# FPGA_APU.net
KiCad netlist of a schematic drawn in EAGLE
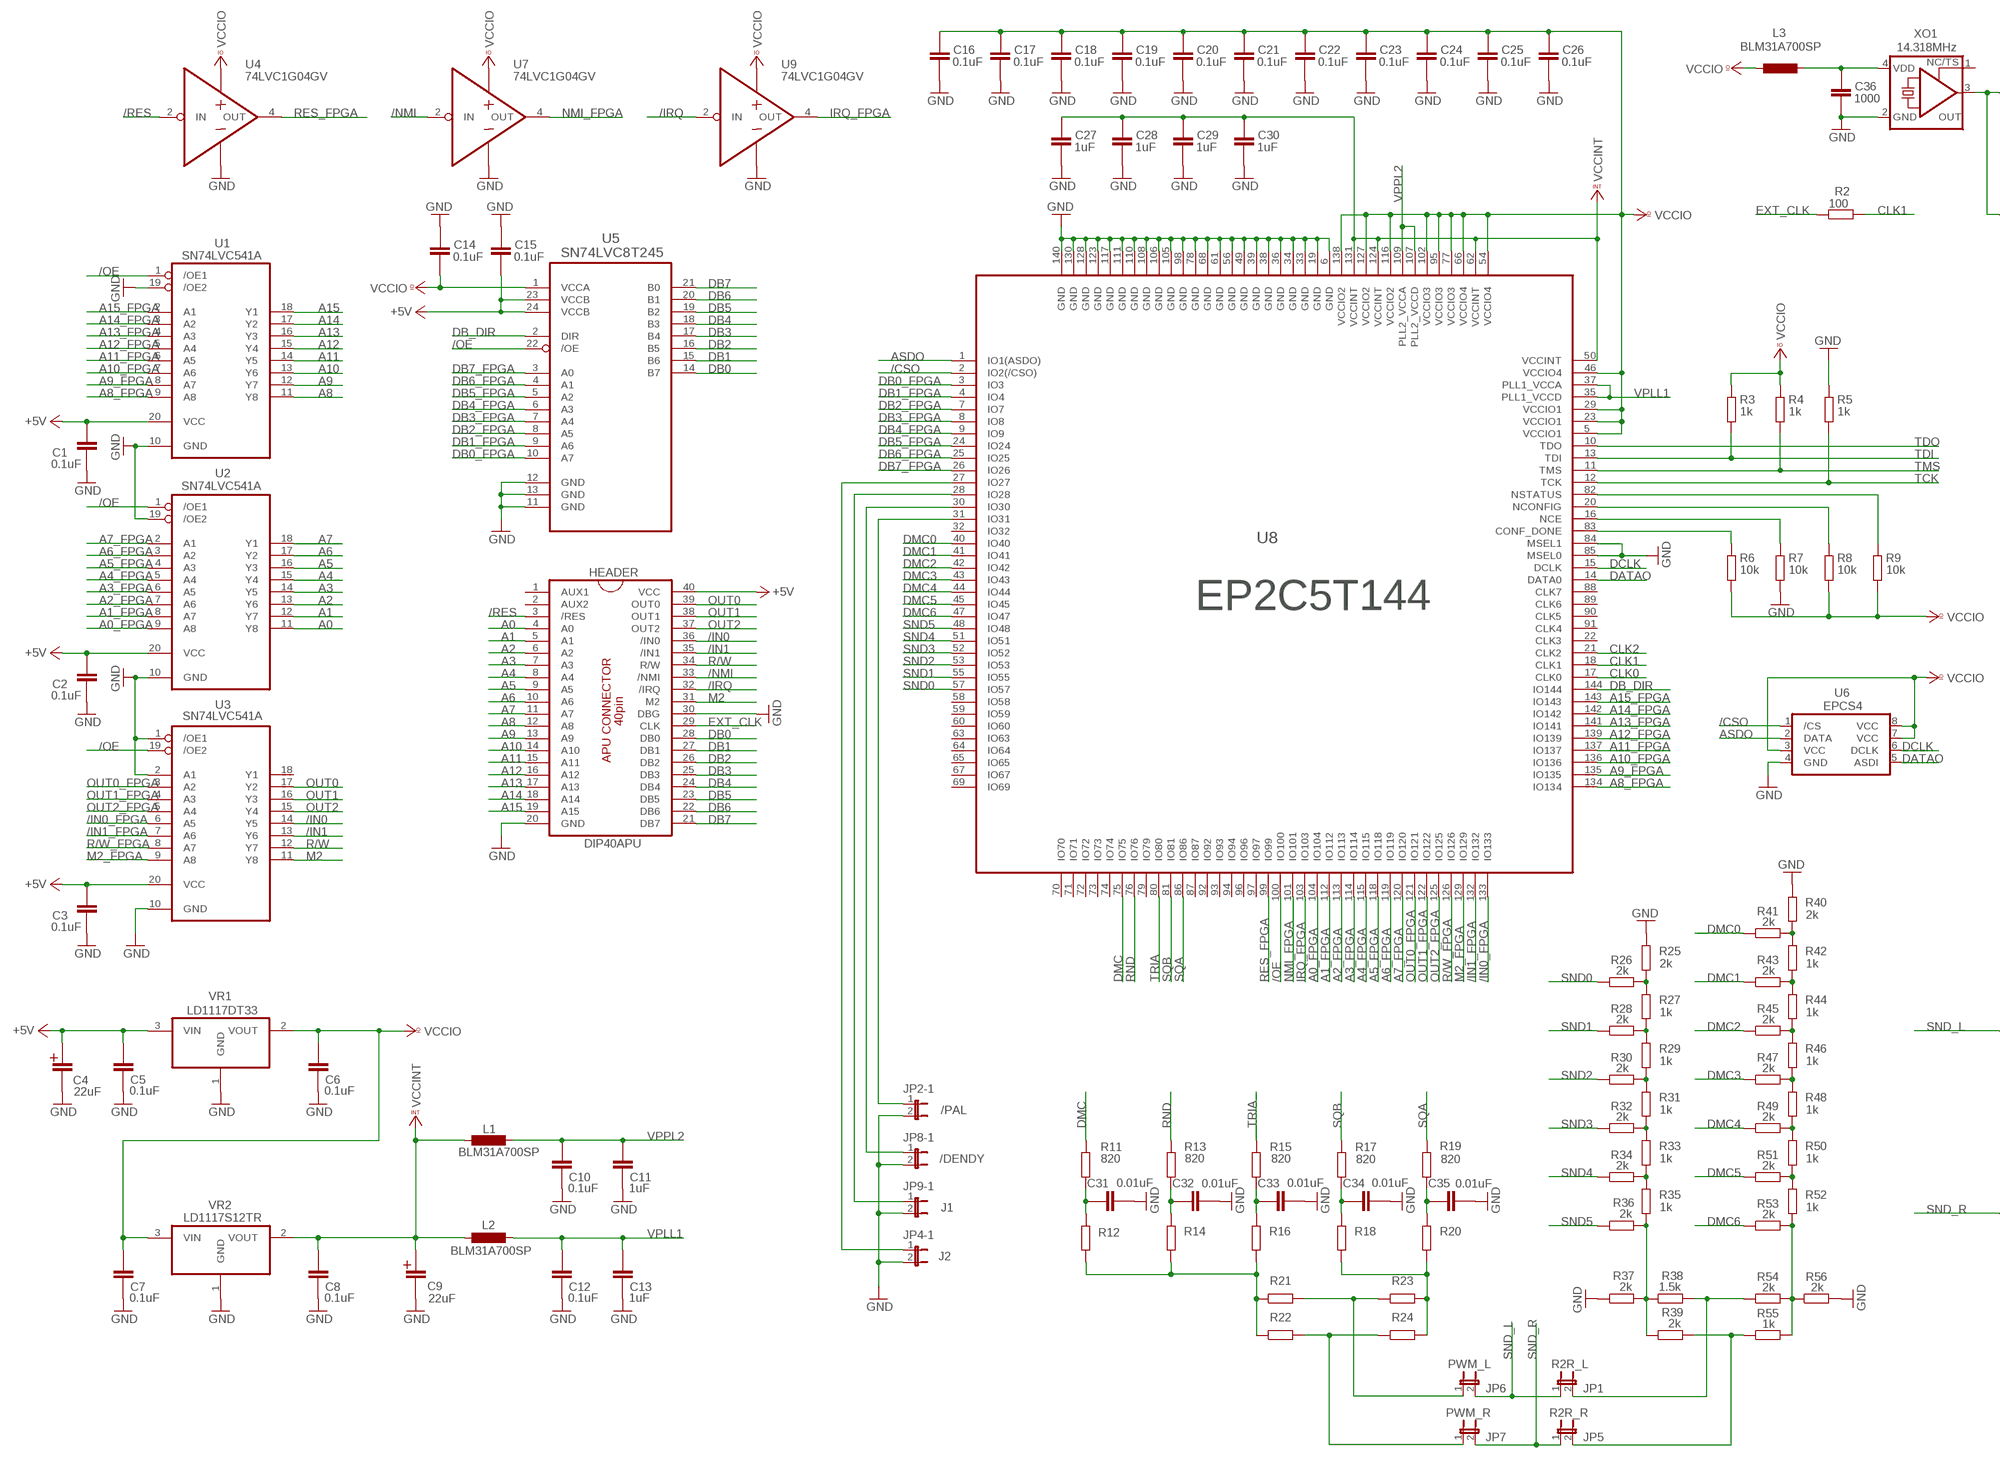
[diagram p0: schematic, sheet 1, part 1 of 2]
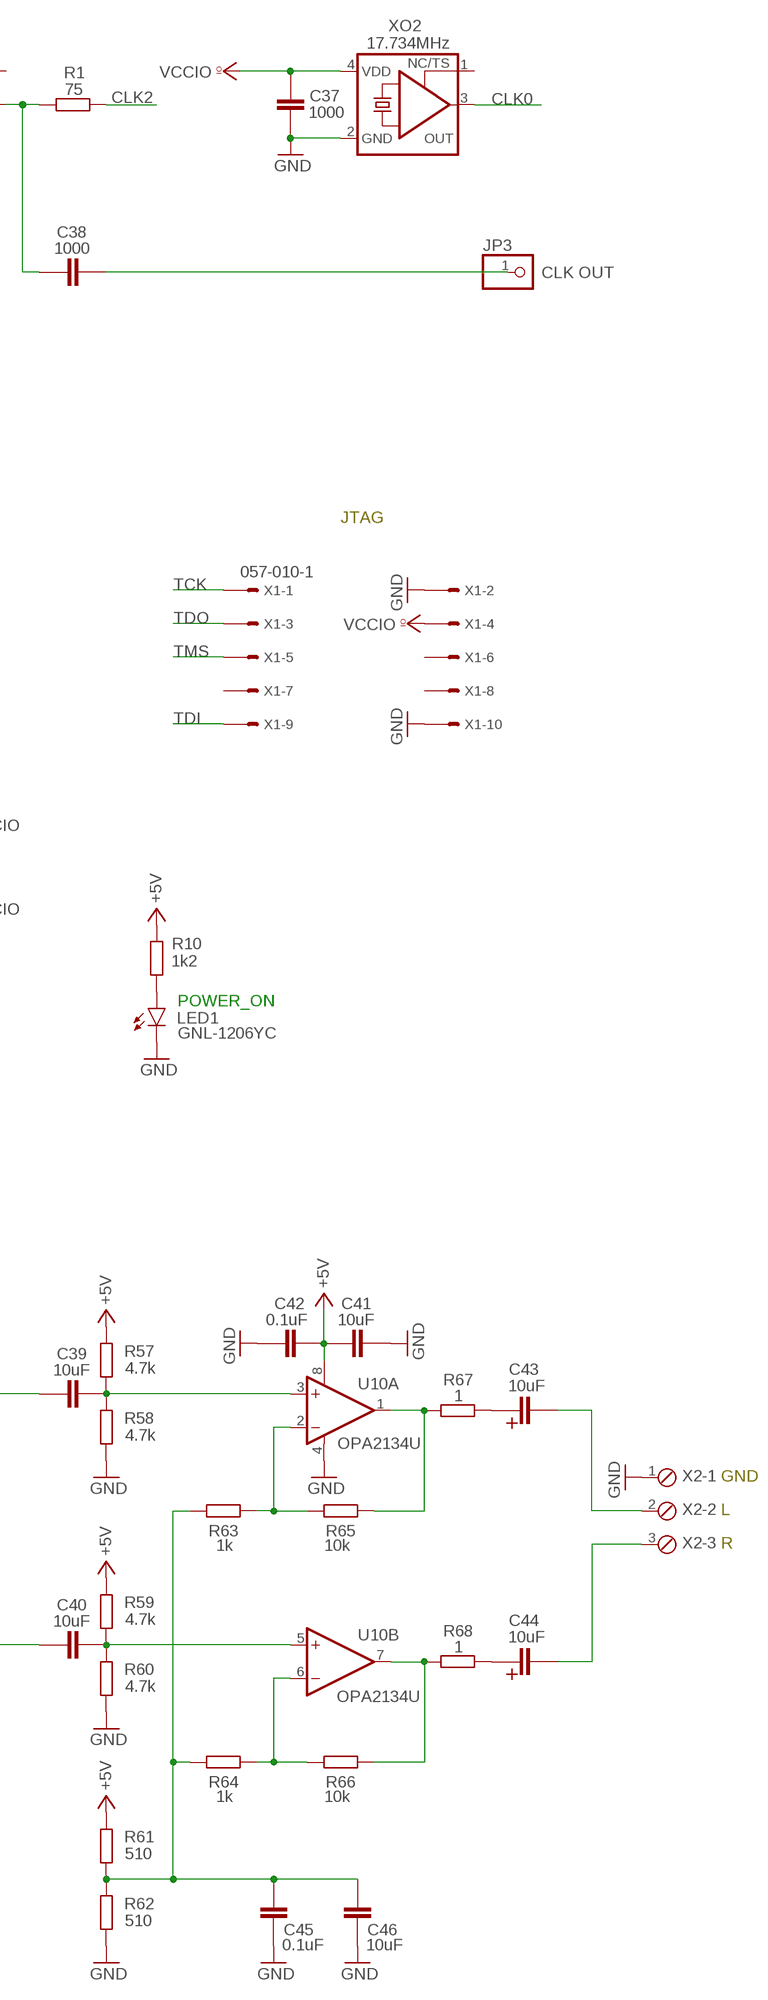
[diagram p1: schematic, sheet 1, part 2 of 2]

(export (version "E")
  (design (tool "Eeschema 10.0.6"))
  (components
    (comp (ref "C1")
      (value "0.1uF")
      (footprint "eagle-import:C0805")
      (libsource (lib "eagle-import") (part "C-EUC0805"))
    )
    (comp (ref "C2")
      (value "0.1uF")
      (footprint "eagle-import:C0805")
      (libsource (lib "eagle-import") (part "C-EUC0805"))
    )
    (comp (ref "C3")
      (value "0.1uF")
      (footprint "eagle-import:C0805")
      (libsource (lib "eagle-import") (part "C-EUC0805"))
    )
    (comp (ref "C4")
      (value "22uF")
      (footprint "eagle-import:153CLV-0505")
      (libsource (lib "eagle-import") (part "CPOL-EU153CLV-0505"))
    )
    (comp (ref "C5")
      (value "0.1uF")
      (footprint "eagle-import:C0805")
      (libsource (lib "eagle-import") (part "C-EUC0805"))
    )
    (comp (ref "C6")
      (value "0.1uF")
      (footprint "eagle-import:C0805")
      (libsource (lib "eagle-import") (part "C-EUC0805"))
    )
    (comp (ref "C7")
      (value "0.1uF")
      (footprint "eagle-import:C0805")
      (libsource (lib "eagle-import") (part "C-EUC0805"))
    )
    (comp (ref "C8")
      (value "0.1uF")
      (footprint "eagle-import:C0805")
      (libsource (lib "eagle-import") (part "C-EUC0805"))
    )
    (comp (ref "C9")
      (value "22uF")
      (footprint "eagle-import:153CLV-0505")
      (libsource (lib "eagle-import") (part "CPOL-EU153CLV-0505"))
    )
    (comp (ref "C10")
      (value "0.1uF")
      (footprint "eagle-import:C0805")
      (libsource (lib "eagle-import") (part "C-EUC0805"))
    )
    (comp (ref "C11")
      (value "1uF")
      (footprint "eagle-import:C0805")
      (libsource (lib "eagle-import") (part "C-EUC0805"))
    )
    (comp (ref "C12")
      (value "0.1uF")
      (footprint "eagle-import:C0805")
      (libsource (lib "eagle-import") (part "C-EUC0805"))
    )
    (comp (ref "C13")
      (value "1uF")
      (footprint "eagle-import:C0805")
      (libsource (lib "eagle-import") (part "C-EUC0805"))
    )
    (comp (ref "C14")
      (value "0.1uF")
      (footprint "eagle-import:C0805")
      (libsource (lib "eagle-import") (part "C-EUC0805"))
    )
    (comp (ref "C15")
      (value "0.1uF")
      (footprint "eagle-import:C0805")
      (libsource (lib "eagle-import") (part "C-EUC0805"))
    )
    (comp (ref "C16")
      (value "0.1uF")
      (footprint "eagle-import:C0805")
      (libsource (lib "eagle-import") (part "C-EUC0805"))
    )
    (comp (ref "C17")
      (value "0.1uF")
      (footprint "eagle-import:C0805")
      (libsource (lib "eagle-import") (part "C-EUC0805"))
    )
    (comp (ref "C18")
      (value "0.1uF")
      (footprint "eagle-import:C0805")
      (libsource (lib "eagle-import") (part "C-EUC0805"))
    )
    (comp (ref "C19")
      (value "0.1uF")
      (footprint "eagle-import:C0805")
      (libsource (lib "eagle-import") (part "C-EUC0805"))
    )
    (comp (ref "C20")
      (value "0.1uF")
      (footprint "eagle-import:C0805")
      (libsource (lib "eagle-import") (part "C-EUC0805"))
    )
    (comp (ref "C21")
      (value "0.1uF")
      (footprint "eagle-import:C0805")
      (libsource (lib "eagle-import") (part "C-EUC0805"))
    )
    (comp (ref "C22")
      (value "0.1uF")
      (footprint "eagle-import:C0805")
      (libsource (lib "eagle-import") (part "C-EUC0805"))
    )
    (comp (ref "C23")
      (value "0.1uF")
      (footprint "eagle-import:C0805")
      (libsource (lib "eagle-import") (part "C-EUC0805"))
    )
    (comp (ref "C24")
      (value "0.1uF")
      (footprint "eagle-import:C0805")
      (libsource (lib "eagle-import") (part "C-EUC0805"))
    )
    (comp (ref "C25")
      (value "0.1uF")
      (footprint "eagle-import:C0805")
      (libsource (lib "eagle-import") (part "C-EUC0805"))
    )
    (comp (ref "C26")
      (value "0.1uF")
      (footprint "eagle-import:C0805")
      (libsource (lib "eagle-import") (part "C-EUC0805"))
    )
    (comp (ref "C27")
      (value "1uF")
      (footprint "eagle-import:C0805")
      (libsource (lib "eagle-import") (part "C-EUC0805"))
    )
    (comp (ref "C28")
      (value "1uF")
      (footprint "eagle-import:C0805")
      (libsource (lib "eagle-import") (part "C-EUC0805"))
    )
    (comp (ref "C29")
      (value "1uF")
      (footprint "eagle-import:C0805")
      (libsource (lib "eagle-import") (part "C-EUC0805"))
    )
    (comp (ref "C30")
      (value "1uF")
      (footprint "eagle-import:C0805")
      (libsource (lib "eagle-import") (part "C-EUC0805"))
    )
    (comp (ref "C31")
      (value "0.01uF")
      (footprint "eagle-import:C0805")
      (libsource (lib "eagle-import") (part "C-EUC0805"))
    )
    (comp (ref "C32")
      (value "0.01uF")
      (footprint "eagle-import:C0805")
      (libsource (lib "eagle-import") (part "C-EUC0805"))
    )
    (comp (ref "C33")
      (value "0.01uF")
      (footprint "eagle-import:C0805")
      (libsource (lib "eagle-import") (part "C-EUC0805"))
    )
    (comp (ref "C34")
      (value "0.01uF")
      (footprint "eagle-import:C0805")
      (libsource (lib "eagle-import") (part "C-EUC0805"))
    )
    (comp (ref "C35")
      (value "0.01uF")
      (footprint "eagle-import:C0805")
      (libsource (lib "eagle-import") (part "C-EUC0805"))
    )
    (comp (ref "C36")
      (value "1000")
      (footprint "eagle-import:C0805")
      (libsource (lib "eagle-import") (part "C-EUC0805"))
    )
    (comp (ref "C37")
      (value "1000")
      (footprint "eagle-import:C0805")
      (libsource (lib "eagle-import") (part "C-EUC0805"))
    )
    (comp (ref "C38")
      (value "1000")
      (footprint "eagle-import:C0805")
      (libsource (lib "eagle-import") (part "C-EUC0805"))
    )
    (comp (ref "C39")
      (value "10uF")
      (footprint "eagle-import:C0805")
      (libsource (lib "eagle-import") (part "C-EUC0805"))
    )
    (comp (ref "C40")
      (value "10uF")
      (footprint "eagle-import:C0805")
      (libsource (lib "eagle-import") (part "C-EUC0805"))
    )
    (comp (ref "C41")
      (value "10uF")
      (footprint "eagle-import:C0805")
      (libsource (lib "eagle-import") (part "C-EUC0805"))
    )
    (comp (ref "C42")
      (value "0.1uF")
      (footprint "eagle-import:C0805")
      (libsource (lib "eagle-import") (part "C-EUC0805"))
    )
    (comp (ref "C43")
      (value "10uF")
      (footprint "eagle-import:153CLV-0505")
      (libsource (lib "eagle-import") (part "CPOL-EU153CLV-0505"))
    )
    (comp (ref "C44")
      (value "10uF")
      (footprint "eagle-import:153CLV-0505")
      (libsource (lib "eagle-import") (part "CPOL-EU153CLV-0505"))
    )
    (comp (ref "C45")
      (value "0.1uF")
      (footprint "eagle-import:C0805")
      (libsource (lib "eagle-import") (part "C-EUC0805"))
    )
    (comp (ref "C46")
      (value "10uF")
      (footprint "eagle-import:C0805")
      (libsource (lib "eagle-import") (part "C-EUC0805"))
    )
    (comp (ref "HEADER")
      (value "DIP40APU")
      (footprint "eagle-import:DIP-40")
      (libsource (lib "eagle-import") (part "DIP40APU"))
    )
    (comp (ref "JP1")
      (value "R2R_L")
      (footprint "eagle-import:JP1")
      (libsource (lib "eagle-import") (part "JP1E"))
    )
    (comp (ref "JP2")
      (value "/PAL")
      (footprint "eagle-import:JP4Q")
      (libsource (lib "eagle-import") (part "JP4QE"))
    )
    (comp (ref "JP3")
      (value "CLK OUT")
      (footprint "eagle-import:1X01")
      (libsource (lib "eagle-import") (part "PINHD-1X1"))
    )
    (comp (ref "JP4")
      (value "J2")
      (footprint "eagle-import:JP4Q")
      (libsource (lib "eagle-import") (part "JP4QE"))
    )
    (comp (ref "JP5")
      (value "R2R_R")
      (footprint "eagle-import:JP1")
      (libsource (lib "eagle-import") (part "JP1E"))
    )
    (comp (ref "JP6")
      (value "PWM_L")
      (footprint "eagle-import:JP1")
      (libsource (lib "eagle-import") (part "JP1E"))
    )
    (comp (ref "JP7")
      (value "PWM_R")
      (footprint "eagle-import:JP1")
      (libsource (lib "eagle-import") (part "JP1E"))
    )
    (comp (ref "JP8")
      (value "/DENDY")
      (footprint "eagle-import:JP4Q")
      (libsource (lib "eagle-import") (part "JP4QE"))
    )
    (comp (ref "JP9")
      (value "J1")
      (footprint "eagle-import:JP4Q")
      (libsource (lib "eagle-import") (part "JP4QE"))
    )
    (comp (ref "L1")
      (value "BLM31A700SP")
      (footprint "eagle-import:L2012C")
      (libsource (lib "eagle-import") (part "L-EUL2012C"))
    )
    (comp (ref "L2")
      (value "BLM31A700SP")
      (footprint "eagle-import:L2012C")
      (libsource (lib "eagle-import") (part "L-EUL2012C"))
    )
    (comp (ref "L3")
      (value "BLM31A700SP")
      (footprint "eagle-import:L2012C")
      (libsource (lib "eagle-import") (part "L-EUL2012C"))
    )
    (comp (ref "LED1")
      (value "GNL-1206YC")
      (footprint "eagle-import:SMARTLED-TTW")
      (libsource (lib "eagle-import") (part "LED"))
    )
    (comp (ref "R1")
      (value "75")
      (footprint "eagle-import:R0805")
      (libsource (lib "eagle-import") (part "R-EU_R0805"))
    )
    (comp (ref "R2")
      (value "100")
      (footprint "eagle-import:R0805")
      (libsource (lib "eagle-import") (part "R-EU_R0805"))
    )
    (comp (ref "R3")
      (value "1k")
      (footprint "eagle-import:R0805")
      (libsource (lib "eagle-import") (part "R-EU_R0805"))
    )
    (comp (ref "R4")
      (value "1k")
      (footprint "eagle-import:R0805")
      (libsource (lib "eagle-import") (part "R-EU_R0805"))
    )
    (comp (ref "R5")
      (value "1k")
      (footprint "eagle-import:R0805")
      (libsource (lib "eagle-import") (part "R-EU_R0805"))
    )
    (comp (ref "R6")
      (value "10k")
      (footprint "eagle-import:R0805")
      (libsource (lib "eagle-import") (part "R-EU_R0805"))
    )
    (comp (ref "R7")
      (value "10k")
      (footprint "eagle-import:R0805")
      (libsource (lib "eagle-import") (part "R-EU_R0805"))
    )
    (comp (ref "R8")
      (value "10k")
      (footprint "eagle-import:R0805")
      (libsource (lib "eagle-import") (part "R-EU_R0805"))
    )
    (comp (ref "R9")
      (value "10k")
      (footprint "eagle-import:R0805")
      (libsource (lib "eagle-import") (part "R-EU_R0805"))
    )
    (comp (ref "R10")
      (value "1k2")
      (footprint "eagle-import:R0805")
      (libsource (lib "eagle-import") (part "R-EU_R0805"))
    )
    (comp (ref "R11")
      (value "820")
      (footprint "eagle-import:R0805")
      (libsource (lib "eagle-import") (part "R-EU_R0805"))
    )
    (comp (ref "R12")
      (value "R-EU_R0805")
      (footprint "eagle-import:R0805")
      (libsource (lib "eagle-import") (part "R-EU_R0805"))
    )
    (comp (ref "R13")
      (value "820")
      (footprint "eagle-import:R0805")
      (libsource (lib "eagle-import") (part "R-EU_R0805"))
    )
    (comp (ref "R14")
      (value "R-EU_R0805")
      (footprint "eagle-import:R0805")
      (libsource (lib "eagle-import") (part "R-EU_R0805"))
    )
    (comp (ref "R15")
      (value "820")
      (footprint "eagle-import:R0805")
      (libsource (lib "eagle-import") (part "R-EU_R0805"))
    )
    (comp (ref "R16")
      (value "R-EU_R0805")
      (footprint "eagle-import:R0805")
      (libsource (lib "eagle-import") (part "R-EU_R0805"))
    )
    (comp (ref "R17")
      (value "820")
      (footprint "eagle-import:R0805")
      (libsource (lib "eagle-import") (part "R-EU_R0805"))
    )
    (comp (ref "R18")
      (value "R-EU_R0805")
      (footprint "eagle-import:R0805")
      (libsource (lib "eagle-import") (part "R-EU_R0805"))
    )
    (comp (ref "R19")
      (value "820")
      (footprint "eagle-import:R0805")
      (libsource (lib "eagle-import") (part "R-EU_R0805"))
    )
    (comp (ref "R20")
      (value "R-EU_R0805")
      (footprint "eagle-import:R0805")
      (libsource (lib "eagle-import") (part "R-EU_R0805"))
    )
    (comp (ref "R21")
      (value "R-EU_R0805")
      (footprint "eagle-import:R0805")
      (libsource (lib "eagle-import") (part "R-EU_R0805"))
    )
    (comp (ref "R22")
      (value "R-EU_R0805")
      (footprint "eagle-import:R0805")
      (libsource (lib "eagle-import") (part "R-EU_R0805"))
    )
    (comp (ref "R23")
      (value "R-EU_R0805")
      (footprint "eagle-import:R0805")
      (libsource (lib "eagle-import") (part "R-EU_R0805"))
    )
    (comp (ref "R24")
      (value "R-EU_R0805")
      (footprint "eagle-import:R0805")
      (libsource (lib "eagle-import") (part "R-EU_R0805"))
    )
    (comp (ref "R25")
      (value "2k")
      (footprint "eagle-import:R0805")
      (libsource (lib "eagle-import") (part "R-EU_R0805"))
    )
    (comp (ref "R26")
      (value "2k")
      (footprint "eagle-import:R0805")
      (libsource (lib "eagle-import") (part "R-EU_R0805"))
    )
    (comp (ref "R27")
      (value "1k")
      (footprint "eagle-import:R0805")
      (libsource (lib "eagle-import") (part "R-EU_R0805"))
    )
    (comp (ref "R28")
      (value "2k")
      (footprint "eagle-import:R0805")
      (libsource (lib "eagle-import") (part "R-EU_R0805"))
    )
    (comp (ref "R29")
      (value "1k")
      (footprint "eagle-import:R0805")
      (libsource (lib "eagle-import") (part "R-EU_R0805"))
    )
    (comp (ref "R30")
      (value "2k")
      (footprint "eagle-import:R0805")
      (libsource (lib "eagle-import") (part "R-EU_R0805"))
    )
    (comp (ref "R31")
      (value "1k")
      (footprint "eagle-import:R0805")
      (libsource (lib "eagle-import") (part "R-EU_R0805"))
    )
    (comp (ref "R32")
      (value "2k")
      (footprint "eagle-import:R0805")
      (libsource (lib "eagle-import") (part "R-EU_R0805"))
    )
    (comp (ref "R33")
      (value "1k")
      (footprint "eagle-import:R0805")
      (libsource (lib "eagle-import") (part "R-EU_R0805"))
    )
    (comp (ref "R34")
      (value "2k")
      (footprint "eagle-import:R0805")
      (libsource (lib "eagle-import") (part "R-EU_R0805"))
    )
    (comp (ref "R35")
      (value "1k")
      (footprint "eagle-import:R0805")
      (libsource (lib "eagle-import") (part "R-EU_R0805"))
    )
    (comp (ref "R36")
      (value "2k")
      (footprint "eagle-import:R0805")
      (libsource (lib "eagle-import") (part "R-EU_R0805"))
    )
    (comp (ref "R37")
      (value "2k")
      (footprint "eagle-import:R0805")
      (libsource (lib "eagle-import") (part "R-EU_R0805"))
    )
    (comp (ref "R38")
      (value "1.5k")
      (footprint "eagle-import:R0805")
      (libsource (lib "eagle-import") (part "R-EU_R0805"))
    )
    (comp (ref "R39")
      (value "2k")
      (footprint "eagle-import:R0805")
      (libsource (lib "eagle-import") (part "R-EU_R0805"))
    )
    (comp (ref "R40")
      (value "2k")
      (footprint "eagle-import:R0805")
      (libsource (lib "eagle-import") (part "R-EU_R0805"))
    )
    (comp (ref "R41")
      (value "2k")
      (footprint "eagle-import:R0805")
      (libsource (lib "eagle-import") (part "R-EU_R0805"))
    )
    (comp (ref "R42")
      (value "1k")
      (footprint "eagle-import:R0805")
      (libsource (lib "eagle-import") (part "R-EU_R0805"))
    )
    (comp (ref "R43")
      (value "2k")
      (footprint "eagle-import:R0805")
      (libsource (lib "eagle-import") (part "R-EU_R0805"))
    )
    (comp (ref "R44")
      (value "1k")
      (footprint "eagle-import:R0805")
      (libsource (lib "eagle-import") (part "R-EU_R0805"))
    )
    (comp (ref "R45")
      (value "2k")
      (footprint "eagle-import:R0805")
      (libsource (lib "eagle-import") (part "R-EU_R0805"))
    )
    (comp (ref "R46")
      (value "1k")
      (footprint "eagle-import:R0805")
      (libsource (lib "eagle-import") (part "R-EU_R0805"))
    )
    (comp (ref "R47")
      (value "2k")
      (footprint "eagle-import:R0805")
      (libsource (lib "eagle-import") (part "R-EU_R0805"))
    )
    (comp (ref "R48")
      (value "1k")
      (footprint "eagle-import:R0805")
      (libsource (lib "eagle-import") (part "R-EU_R0805"))
    )
    (comp (ref "R49")
      (value "2k")
      (footprint "eagle-import:R0805")
      (libsource (lib "eagle-import") (part "R-EU_R0805"))
    )
    (comp (ref "R50")
      (value "1k")
      (footprint "eagle-import:R0805")
      (libsource (lib "eagle-import") (part "R-EU_R0805"))
    )
    (comp (ref "R51")
      (value "2k")
      (footprint "eagle-import:R0805")
      (libsource (lib "eagle-import") (part "R-EU_R0805"))
    )
    (comp (ref "R52")
      (value "1k")
      (footprint "eagle-import:R0805")
      (libsource (lib "eagle-import") (part "R-EU_R0805"))
    )
    (comp (ref "R53")
      (value "2k")
      (footprint "eagle-import:R0805")
      (libsource (lib "eagle-import") (part "R-EU_R0805"))
    )
    (comp (ref "R54")
      (value "2k")
      (footprint "eagle-import:R0805")
      (libsource (lib "eagle-import") (part "R-EU_R0805"))
    )
    (comp (ref "R55")
      (value "1k")
      (footprint "eagle-import:R0805")
      (libsource (lib "eagle-import") (part "R-EU_R0805"))
    )
    (comp (ref "R56")
      (value "2k")
      (footprint "eagle-import:R0805")
      (libsource (lib "eagle-import") (part "R-EU_R0805"))
    )
    (comp (ref "R57")
      (value "4.7k")
      (footprint "eagle-import:R0805")
      (libsource (lib "eagle-import") (part "R-EU_R0805"))
    )
    (comp (ref "R58")
      (value "4.7k")
      (footprint "eagle-import:R0805")
      (libsource (lib "eagle-import") (part "R-EU_R0805"))
    )
    (comp (ref "R59")
      (value "4.7k")
      (footprint "eagle-import:R0805")
      (libsource (lib "eagle-import") (part "R-EU_R0805"))
    )
    (comp (ref "R60")
      (value "4.7k")
      (footprint "eagle-import:R0805")
      (libsource (lib "eagle-import") (part "R-EU_R0805"))
    )
    (comp (ref "R61")
      (value "510")
      (footprint "eagle-import:R0805")
      (libsource (lib "eagle-import") (part "R-EU_R0805"))
    )
    (comp (ref "R62")
      (value "510")
      (footprint "eagle-import:R0805")
      (libsource (lib "eagle-import") (part "R-EU_R0805"))
    )
    (comp (ref "R63")
      (value "1k")
      (footprint "eagle-import:R0805")
      (libsource (lib "eagle-import") (part "R-EU_R0805"))
    )
    (comp (ref "R64")
      (value "1k")
      (footprint "eagle-import:R0805")
      (libsource (lib "eagle-import") (part "R-EU_R0805"))
    )
    (comp (ref "R65")
      (value "10k")
      (footprint "eagle-import:R0805")
      (libsource (lib "eagle-import") (part "R-EU_R0805"))
    )
    (comp (ref "R66")
      (value "10k")
      (footprint "eagle-import:R0805")
      (libsource (lib "eagle-import") (part "R-EU_R0805"))
    )
    (comp (ref "R67")
      (value "1")
      (footprint "eagle-import:R0805")
      (libsource (lib "eagle-import") (part "R-EU_R0805"))
    )
    (comp (ref "R68")
      (value "1")
      (footprint "eagle-import:R0805")
      (libsource (lib "eagle-import") (part "R-EU_R0805"))
    )
    (comp (ref "U1")
      (value "SN74LVC541A")
      (footprint "eagle-import:TSOP20")
      (libsource (lib "eagle-import") (part "SN74LVC541A"))
    )
    (comp (ref "U2")
      (value "SN74LVC541A")
      (footprint "eagle-import:TSOP20")
      (libsource (lib "eagle-import") (part "SN74LVC541A"))
    )
    (comp (ref "U3")
      (value "SN74LVC541A")
      (footprint "eagle-import:TSOP20")
      (libsource (lib "eagle-import") (part "SN74LVC541A"))
    )
    (comp (ref "U4")
      (value "74LVC1G04GV")
      (footprint "eagle-import:SOT95P275X110-5N")
      (libsource (lib "eagle-import") (part "74LVC1G04GV"))
    )
    (comp (ref "U5")
      (value "SN74LVC8T245")
      (footprint "eagle-import:SOP65P640X110-24N")
      (libsource (lib "eagle-import") (part "SN74LVC8T245"))
    )
    (comp (ref "U6")
      (value "EPCS4")
      (footprint "eagle-import:SO08")
      (libsource (lib "eagle-import") (part "EPCS4"))
    )
    (comp (ref "U7")
      (value "74LVC1G04GV")
      (footprint "eagle-import:SOT95P275X110-5N")
      (libsource (lib "eagle-import") (part "74LVC1G04GV"))
    )
    (comp (ref "U8")
      (value "EP2C5T144")
      (footprint "eagle-import:TQFP144")
      (fields (field (name "MPN") "EP2C5T144C8N"))
      (libsource (lib "eagle-import") (part "EP2C5T144"))
    )
    (comp (ref "U9")
      (value "74LVC1G04GV")
      (footprint "eagle-import:SOT95P275X110-5N")
      (libsource (lib "eagle-import") (part "74LVC1G04GV"))
    )
    (comp (ref "U10")
      (value "OPA2134U")
      (footprint "eagle-import:SO08")
      (fields (field (name "MF") "TEXAS INSTRUMENTS") (field (name "MPN") "OPA2134UA"))
      (libsource (lib "eagle-import") (part "OPA2134U"))
    )
    (comp (ref "VR1")
      (value "LD1117DT33")
      (footprint "eagle-import:DPAK456P1010X240-3N")
      (fields (field (name "MANUFACTURER") "STMicroelectronics"))
      (libsource (lib "eagle-import") (part "LD1117DT33"))
    )
    (comp (ref "VR2")
      (value "LD1117S12TR")
      (footprint "eagle-import:SOT-223-3")
      (libsource (lib "eagle-import") (part "LD1117S12TR"))
    )
    (comp (ref "X1")
      (value "057-010-1")
      (footprint "eagle-import:057-010-1")
      (libsource (lib "eagle-import") (part "057-010-1"))
    )
    (comp (ref "X2")
      (value "OUT")
      (footprint "eagle-import:7POL254")
      (libsource (lib "eagle-import") (part "MPT7"))
    )
    (comp (ref "XO1")
      (value "14.318MHz")
      (footprint "eagle-import:7.0X5.08_KXO-(V)97")
      (libsource (lib "eagle-import") (part "KXO-PXO/XO-V97"))
    )
    (comp (ref "XO2")
      (value "17.734MHz")
      (footprint "eagle-import:2.5X2.0_KXO-V95")
      (libsource (lib "eagle-import") (part "KXO-PXO/XO-V95"))
    )
  )
  (nets
    (net (code "1") (name "+5V") (class "Default")
      (node (ref "C1") (pin "1") (pinfunction "1_1") (pintype "passive"))
      (node (ref "C15") (pin "2") (pinfunction "2_2") (pintype "passive"))
      (node (ref "C2") (pin "1") (pinfunction "1_1") (pintype "passive"))
      (node (ref "C3") (pin "1") (pinfunction "1_1") (pintype "passive"))
      (node (ref "C4") (pin "+") (pinfunction "+_+") (pintype "passive"))
      (node (ref "C41") (pin "1") (pinfunction "1_1") (pintype "passive"))
      (node (ref "C42") (pin "2") (pinfunction "2_2") (pintype "passive"))
      (node (ref "C5") (pin "1") (pinfunction "1_1") (pintype "passive"))
      (node (ref "HEADER") (pin "40") (pinfunction "VCC_40") (pintype "power_in"))
      (node (ref "R10") (pin "2") (pinfunction "2_2") (pintype "passive"))
      (node (ref "R57") (pin "1") (pinfunction "1_1") (pintype "passive"))
      (node (ref "R59") (pin "1") (pinfunction "1_1") (pintype "passive"))
      (node (ref "R61") (pin "1") (pinfunction "1_1") (pintype "passive"))
      (node (ref "U1") (pin "20") (pinfunction "VCC_20") (pintype "power_in"))
      (node (ref "U10") (pin "8") (pinfunction "V+_8") (pintype "power_in"))
      (node (ref "U2") (pin "20") (pinfunction "VCC_20") (pintype "power_in"))
      (node (ref "U3") (pin "20") (pinfunction "VCC_20") (pintype "power_in"))
      (node (ref "U5") (pin "23") (pinfunction "VCCB_23") (pintype "power_in"))
      (node (ref "U5") (pin "24") (pinfunction "VCCB_24") (pintype "power_in"))
      (node (ref "VR1") (pin "3") (pinfunction "VIN_3") (pintype "power_in"))
    )
    (net (code "2") (name "/A0") (class "Default")
      (node (ref "HEADER") (pin "4") (pinfunction "A0_4") (pintype "input"))
      (node (ref "U2") (pin "11") (pinfunction "Y8_11") (pintype "output"))
    )
    (net (code "3") (name "/A0_FPGA") (class "Default")
      (node (ref "U2") (pin "9") (pinfunction "A8_9") (pintype "input"))
      (node (ref "U8") (pin "104") (pinfunction "IO104_104") (pintype "bidirectional"))
    )
    (net (code "4") (name "/A1") (class "Default")
      (node (ref "HEADER") (pin "5") (pinfunction "A1_5") (pintype "input"))
      (node (ref "U2") (pin "12") (pinfunction "Y7_12") (pintype "output"))
    )
    (net (code "5") (name "/A1_FPGA") (class "Default")
      (node (ref "U2") (pin "8") (pinfunction "A7_8") (pintype "input"))
      (node (ref "U8") (pin "112") (pinfunction "IO112_112") (pintype "bidirectional"))
    )
    (net (code "6") (name "/A2") (class "Default")
      (node (ref "HEADER") (pin "6") (pinfunction "A2_6") (pintype "input"))
      (node (ref "U2") (pin "13") (pinfunction "Y6_13") (pintype "output"))
    )
    (net (code "7") (name "/A2_FPGA") (class "Default")
      (node (ref "U2") (pin "7") (pinfunction "A6_7") (pintype "input"))
      (node (ref "U8") (pin "113") (pinfunction "IO113_113") (pintype "bidirectional"))
    )
    (net (code "8") (name "/A3") (class "Default")
      (node (ref "HEADER") (pin "7") (pinfunction "A3_7") (pintype "input"))
      (node (ref "U2") (pin "14") (pinfunction "Y5_14") (pintype "output"))
    )
    (net (code "9") (name "/A3_FPGA") (class "Default")
      (node (ref "U2") (pin "6") (pinfunction "A5_6") (pintype "input"))
      (node (ref "U8") (pin "114") (pinfunction "IO114_114") (pintype "bidirectional"))
    )
    (net (code "10") (name "/A4") (class "Default")
      (node (ref "HEADER") (pin "8") (pinfunction "A4_8") (pintype "input"))
      (node (ref "U2") (pin "15") (pinfunction "Y4_15") (pintype "output"))
    )
    (net (code "11") (name "/A4_FPGA") (class "Default")
      (node (ref "U2") (pin "5") (pinfunction "A4_5") (pintype "input"))
      (node (ref "U8") (pin "115") (pinfunction "IO115_115") (pintype "bidirectional"))
    )
    (net (code "12") (name "/A5") (class "Default")
      (node (ref "HEADER") (pin "9") (pinfunction "A5_9") (pintype "input"))
      (node (ref "U2") (pin "16") (pinfunction "Y3_16") (pintype "output"))
    )
    (net (code "13") (name "/A5_FPGA") (class "Default")
      (node (ref "U2") (pin "4") (pinfunction "A3_4") (pintype "input"))
      (node (ref "U8") (pin "118") (pinfunction "IO118_118") (pintype "bidirectional"))
    )
    (net (code "14") (name "/A6") (class "Default")
      (node (ref "HEADER") (pin "10") (pinfunction "A6_10") (pintype "input"))
      (node (ref "U2") (pin "17") (pinfunction "Y2_17") (pintype "output"))
    )
    (net (code "15") (name "/A6_FPGA") (class "Default")
      (node (ref "U2") (pin "3") (pinfunction "A2_3") (pintype "input"))
      (node (ref "U8") (pin "119") (pinfunction "IO119_119") (pintype "bidirectional"))
    )
    (net (code "16") (name "/A7") (class "Default")
      (node (ref "HEADER") (pin "11") (pinfunction "A7_11") (pintype "input"))
      (node (ref "U2") (pin "18") (pinfunction "Y1_18") (pintype "output"))
    )
    (net (code "17") (name "/A7_FPGA") (class "Default")
      (node (ref "U2") (pin "2") (pinfunction "A1_2") (pintype "input"))
      (node (ref "U8") (pin "120") (pinfunction "IO120_120") (pintype "bidirectional"))
    )
    (net (code "18") (name "/A8") (class "Default")
      (node (ref "HEADER") (pin "12") (pinfunction "A8_12") (pintype "input"))
      (node (ref "U1") (pin "11") (pinfunction "Y8_11") (pintype "output"))
    )
    (net (code "19") (name "/A8_FPGA") (class "Default")
      (node (ref "U1") (pin "9") (pinfunction "A8_9") (pintype "input"))
      (node (ref "U8") (pin "134") (pinfunction "IO134_134") (pintype "bidirectional"))
    )
    (net (code "20") (name "/A9") (class "Default")
      (node (ref "HEADER") (pin "13") (pinfunction "A9_13") (pintype "input"))
      (node (ref "U1") (pin "12") (pinfunction "Y7_12") (pintype "output"))
    )
    (net (code "21") (name "/A9_FPGA") (class "Default")
      (node (ref "U1") (pin "8") (pinfunction "A7_8") (pintype "input"))
      (node (ref "U8") (pin "135") (pinfunction "IO135_135") (pintype "bidirectional"))
    )
    (net (code "22") (name "/A10") (class "Default")
      (node (ref "HEADER") (pin "14") (pinfunction "A10_14") (pintype "input"))
      (node (ref "U1") (pin "13") (pinfunction "Y6_13") (pintype "output"))
    )
    (net (code "23") (name "/A10_FPGA") (class "Default")
      (node (ref "U1") (pin "7") (pinfunction "A6_7") (pintype "input"))
      (node (ref "U8") (pin "136") (pinfunction "IO136_136") (pintype "bidirectional"))
    )
    (net (code "24") (name "/A11") (class "Default")
      (node (ref "HEADER") (pin "15") (pinfunction "A11_15") (pintype "input"))
      (node (ref "U1") (pin "14") (pinfunction "Y5_14") (pintype "output"))
    )
    (net (code "25") (name "/A11_FPGA") (class "Default")
      (node (ref "U1") (pin "6") (pinfunction "A5_6") (pintype "input"))
      (node (ref "U8") (pin "137") (pinfunction "IO137_137") (pintype "bidirectional"))
    )
    (net (code "26") (name "/A12") (class "Default")
      (node (ref "HEADER") (pin "16") (pinfunction "A12_16") (pintype "input"))
      (node (ref "U1") (pin "15") (pinfunction "Y4_15") (pintype "output"))
    )
    (net (code "27") (name "/A12_FPGA") (class "Default")
      (node (ref "U1") (pin "5") (pinfunction "A4_5") (pintype "input"))
      (node (ref "U8") (pin "139") (pinfunction "IO139_139") (pintype "bidirectional"))
    )
    (net (code "28") (name "/A13") (class "Default")
      (node (ref "HEADER") (pin "17") (pinfunction "A13_17") (pintype "input"))
      (node (ref "U1") (pin "16") (pinfunction "Y3_16") (pintype "output"))
    )
    (net (code "29") (name "/A13_FPGA") (class "Default")
      (node (ref "U1") (pin "4") (pinfunction "A3_4") (pintype "input"))
      (node (ref "U8") (pin "141") (pinfunction "IO141_141") (pintype "bidirectional"))
    )
    (net (code "30") (name "/A14") (class "Default")
      (node (ref "HEADER") (pin "18") (pinfunction "A14_18") (pintype "input"))
      (node (ref "U1") (pin "17") (pinfunction "Y2_17") (pintype "output"))
    )
    (net (code "31") (name "/A14_FPGA") (class "Default")
      (node (ref "U1") (pin "3") (pinfunction "A2_3") (pintype "input"))
      (node (ref "U8") (pin "142") (pinfunction "IO142_142") (pintype "bidirectional"))
    )
    (net (code "32") (name "/A15") (class "Default")
      (node (ref "HEADER") (pin "19") (pinfunction "A15_19") (pintype "input"))
      (node (ref "U1") (pin "18") (pinfunction "Y1_18") (pintype "output"))
    )
    (net (code "33") (name "/A15_FPGA") (class "Default")
      (node (ref "U1") (pin "2") (pinfunction "A1_2") (pintype "input"))
      (node (ref "U8") (pin "143") (pinfunction "IO143_143") (pintype "bidirectional"))
    )
    (net (code "34") (name "/ASDO") (class "Default")
      (node (ref "U6") (pin "2") (pinfunction "DATA_2") (pintype "output"))
      (node (ref "U8") (pin "1") (pinfunction "IO1(ASDO)_1") (pintype "output"))
    )
    (net (code "35") (name "/CLK0") (class "Default")
      (node (ref "U8") (pin "17") (pinfunction "CLK0_17") (pintype "bidirectional"))
      (node (ref "XO2") (pin "3") (pinfunction "OUT_3") (pintype "output"))
    )
    (net (code "36") (name "/CLK1") (class "Default")
      (node (ref "R2") (pin "2") (pinfunction "2_2") (pintype "passive"))
      (node (ref "U8") (pin "18") (pinfunction "CLK1_18") (pintype "bidirectional"))
    )
    (net (code "37") (name "/CLK2") (class "Default")
      (node (ref "R1") (pin "2") (pinfunction "2_2") (pintype "passive"))
      (node (ref "U8") (pin "21") (pinfunction "CLK2_21") (pintype "bidirectional"))
    )
    (net (code "38") (name "/DATAO") (class "Default")
      (node (ref "U6") (pin "5") (pinfunction "ASDI_5") (pintype "input"))
      (node (ref "U8") (pin "14") (pinfunction "DATA0_14") (pintype "bidirectional"))
    )
    (net (code "39") (name "/DB0") (class "Default")
      (node (ref "HEADER") (pin "28") (pinfunction "DB0_28") (pintype "bidirectional"))
      (node (ref "U5") (pin "14") (pinfunction "B7_14") (pintype "bidirectional"))
    )
    (net (code "40") (name "/DB0_FPGA") (class "Default")
      (node (ref "U5") (pin "10") (pinfunction "A7_10") (pintype "bidirectional"))
      (node (ref "U8") (pin "3") (pinfunction "IO3_3") (pintype "bidirectional"))
    )
    (net (code "41") (name "/DB1") (class "Default")
      (node (ref "HEADER") (pin "27") (pinfunction "DB1_27") (pintype "bidirectional"))
      (node (ref "U5") (pin "15") (pinfunction "B6_15") (pintype "bidirectional"))
    )
    (net (code "42") (name "/DB1_FPGA") (class "Default")
      (node (ref "U5") (pin "9") (pinfunction "A6_9") (pintype "bidirectional"))
      (node (ref "U8") (pin "4") (pinfunction "IO4_4") (pintype "bidirectional"))
    )
    (net (code "43") (name "/DB2") (class "Default")
      (node (ref "HEADER") (pin "26") (pinfunction "DB2_26") (pintype "bidirectional"))
      (node (ref "U5") (pin "16") (pinfunction "B5_16") (pintype "bidirectional"))
    )
    (net (code "44") (name "/DB2_FPGA") (class "Default")
      (node (ref "U5") (pin "8") (pinfunction "A5_8") (pintype "bidirectional"))
      (node (ref "U8") (pin "7") (pinfunction "IO7_7") (pintype "bidirectional"))
    )
    (net (code "45") (name "/DB3") (class "Default")
      (node (ref "HEADER") (pin "25") (pinfunction "DB3_25") (pintype "bidirectional"))
      (node (ref "U5") (pin "17") (pinfunction "B4_17") (pintype "bidirectional"))
    )
    (net (code "46") (name "/DB3_FPGA") (class "Default")
      (node (ref "U5") (pin "7") (pinfunction "A4_7") (pintype "bidirectional"))
      (node (ref "U8") (pin "8") (pinfunction "IO8_8") (pintype "bidirectional"))
    )
    (net (code "47") (name "/DB4") (class "Default")
      (node (ref "HEADER") (pin "24") (pinfunction "DB4_24") (pintype "bidirectional"))
      (node (ref "U5") (pin "18") (pinfunction "B3_18") (pintype "bidirectional"))
    )
    (net (code "48") (name "/DB4_FPGA") (class "Default")
      (node (ref "U5") (pin "6") (pinfunction "A3_6") (pintype "bidirectional"))
      (node (ref "U8") (pin "9") (pinfunction "IO9_9") (pintype "bidirectional"))
    )
    (net (code "49") (name "/DB5") (class "Default")
      (node (ref "HEADER") (pin "23") (pinfunction "DB5_23") (pintype "bidirectional"))
      (node (ref "U5") (pin "19") (pinfunction "B2_19") (pintype "bidirectional"))
    )
    (net (code "50") (name "/DB5_FPGA") (class "Default")
      (node (ref "U5") (pin "5") (pinfunction "A2_5") (pintype "bidirectional"))
      (node (ref "U8") (pin "24") (pinfunction "IO24_24") (pintype "bidirectional"))
    )
    (net (code "51") (name "/DB6") (class "Default")
      (node (ref "HEADER") (pin "22") (pinfunction "DB6_22") (pintype "bidirectional"))
      (node (ref "U5") (pin "20") (pinfunction "B1_20") (pintype "bidirectional"))
    )
    (net (code "52") (name "/DB6_FPGA") (class "Default")
      (node (ref "U5") (pin "4") (pinfunction "A1_4") (pintype "bidirectional"))
      (node (ref "U8") (pin "25") (pinfunction "IO25_25") (pintype "bidirectional"))
    )
    (net (code "53") (name "/DB7") (class "Default")
      (node (ref "HEADER") (pin "21") (pinfunction "DB7_21") (pintype "bidirectional"))
      (node (ref "U5") (pin "21") (pinfunction "B0_21") (pintype "bidirectional"))
    )
    (net (code "54") (name "/DB7_FPGA") (class "Default")
      (node (ref "U5") (pin "3") (pinfunction "A0_3") (pintype "bidirectional"))
      (node (ref "U8") (pin "26") (pinfunction "IO26_26") (pintype "bidirectional"))
    )
    (net (code "55") (name "/DB_DIR") (class "Default")
      (node (ref "U5") (pin "2") (pinfunction "DIR_2") (pintype "input"))
      (node (ref "U8") (pin "144") (pinfunction "IO144_144") (pintype "bidirectional"))
    )
    (net (code "56") (name "/DCLK") (class "Default")
      (node (ref "U6") (pin "6") (pinfunction "DCLK_6") (pintype "input"))
      (node (ref "U8") (pin "15") (pinfunction "DCLK_15") (pintype "bidirectional"))
    )
    (net (code "57") (name "/DMC") (class "Default")
      (node (ref "R11") (pin "1") (pinfunction "1_1") (pintype "passive"))
      (node (ref "U8") (pin "75") (pinfunction "IO75_75") (pintype "bidirectional"))
    )
    (net (code "58") (name "/DMC0") (class "Default")
      (node (ref "R41") (pin "1") (pinfunction "1_1") (pintype "passive"))
      (node (ref "U8") (pin "40") (pinfunction "IO40_40") (pintype "bidirectional"))
    )
    (net (code "59") (name "/DMC1") (class "Default")
      (node (ref "R43") (pin "1") (pinfunction "1_1") (pintype "passive"))
      (node (ref "U8") (pin "41") (pinfunction "IO41_41") (pintype "bidirectional"))
    )
    (net (code "60") (name "/DMC2") (class "Default")
      (node (ref "R45") (pin "1") (pinfunction "1_1") (pintype "passive"))
      (node (ref "U8") (pin "42") (pinfunction "IO42_42") (pintype "bidirectional"))
    )
    (net (code "61") (name "/DMC3") (class "Default")
      (node (ref "R47") (pin "1") (pinfunction "1_1") (pintype "passive"))
      (node (ref "U8") (pin "43") (pinfunction "IO43_43") (pintype "bidirectional"))
    )
    (net (code "62") (name "/DMC4") (class "Default")
      (node (ref "R49") (pin "1") (pinfunction "1_1") (pintype "passive"))
      (node (ref "U8") (pin "44") (pinfunction "IO44_44") (pintype "bidirectional"))
    )
    (net (code "63") (name "/DMC5") (class "Default")
      (node (ref "R51") (pin "1") (pinfunction "1_1") (pintype "passive"))
      (node (ref "U8") (pin "45") (pinfunction "IO45_45") (pintype "bidirectional"))
    )
    (net (code "64") (name "/DMC6") (class "Default")
      (node (ref "R53") (pin "1") (pinfunction "1_1") (pintype "passive"))
      (node (ref "U8") (pin "47") (pinfunction "IO47_47") (pintype "bidirectional"))
    )
    (net (code "65") (name "/EXT_CLK") (class "Default")
      (node (ref "HEADER") (pin "29") (pinfunction "CLK_29") (pintype "output"))
      (node (ref "R2") (pin "1") (pinfunction "1_1") (pintype "passive"))
    )
    (net (code "66") (name "/IRQ_FPGA") (class "Default")
      (node (ref "U8") (pin "103") (pinfunction "IO103_103") (pintype "bidirectional"))
      (node (ref "U9") (pin "4") (pinfunction "OUT_4") (pintype "bidirectional"))
    )
    (net (code "67") (name "/M2") (class "Default")
      (node (ref "HEADER") (pin "31") (pinfunction "M2_31") (pintype "input"))
      (node (ref "U3") (pin "11") (pinfunction "Y8_11") (pintype "output"))
    )
    (net (code "68") (name "/M2_FPGA") (class "Default")
      (node (ref "U3") (pin "9") (pinfunction "A8_9") (pintype "input"))
      (node (ref "U8") (pin "129") (pinfunction "IO129_129") (pintype "bidirectional"))
    )
    (net (code "69") (name "/NMI_FPGA") (class "Default")
      (node (ref "U7") (pin "4") (pinfunction "OUT_4") (pintype "bidirectional"))
      (node (ref "U8") (pin "101") (pinfunction "IO101_101") (pintype "bidirectional"))
    )
    (net (code "70") (name "/OUT0") (class "Default")
      (node (ref "HEADER") (pin "39") (pinfunction "OUT0_39") (pintype "input"))
      (node (ref "U3") (pin "17") (pinfunction "Y2_17") (pintype "output"))
    )
    (net (code "71") (name "/OUT0_FPGA") (class "Default")
      (node (ref "U3") (pin "3") (pinfunction "A2_3") (pintype "input"))
      (node (ref "U8") (pin "121") (pinfunction "IO121_121") (pintype "bidirectional"))
    )
    (net (code "72") (name "/OUT1") (class "Default")
      (node (ref "HEADER") (pin "38") (pinfunction "OUT1_38") (pintype "input"))
      (node (ref "U3") (pin "16") (pinfunction "Y3_16") (pintype "output"))
    )
    (net (code "73") (name "/OUT1_FPGA") (class "Default")
      (node (ref "U3") (pin "4") (pinfunction "A3_4") (pintype "input"))
      (node (ref "U8") (pin "122") (pinfunction "IO122_122") (pintype "bidirectional"))
    )
    (net (code "74") (name "/OUT2") (class "Default")
      (node (ref "HEADER") (pin "37") (pinfunction "OUT2_37") (pintype "input"))
      (node (ref "U3") (pin "15") (pinfunction "Y4_15") (pintype "output"))
    )
    (net (code "75") (name "/OUT2_FPGA") (class "Default")
      (node (ref "U3") (pin "5") (pinfunction "A4_5") (pintype "input"))
      (node (ref "U8") (pin "125") (pinfunction "IO125_125") (pintype "bidirectional"))
    )
    (net (code "76") (name "/RES_FPGA") (class "Default")
      (node (ref "U4") (pin "4") (pinfunction "OUT_4") (pintype "bidirectional"))
      (node (ref "U8") (pin "99") (pinfunction "IO99_99") (pintype "bidirectional"))
    )
    (net (code "77") (name "/RND") (class "Default")
      (node (ref "R13") (pin "1") (pinfunction "1_1") (pintype "passive"))
      (node (ref "U8") (pin "76") (pinfunction "IO76_76") (pintype "bidirectional"))
    )
    (net (code "78") (name "/R{slash}W") (class "Default")
      (node (ref "HEADER") (pin "34") (pinfunction "R/W_34") (pintype "input"))
      (node (ref "U3") (pin "12") (pinfunction "Y7_12") (pintype "output"))
    )
    (net (code "79") (name "/R{slash}W_FPGA") (class "Default")
      (node (ref "U3") (pin "8") (pinfunction "A7_8") (pintype "input"))
      (node (ref "U8") (pin "126") (pinfunction "IO126_126") (pintype "bidirectional"))
    )
    (net (code "80") (name "/SND0") (class "Default")
      (node (ref "R26") (pin "1") (pinfunction "1_1") (pintype "passive"))
      (node (ref "U8") (pin "57") (pinfunction "IO57_57") (pintype "bidirectional"))
    )
    (net (code "81") (name "/SND1") (class "Default")
      (node (ref "R28") (pin "1") (pinfunction "1_1") (pintype "passive"))
      (node (ref "U8") (pin "55") (pinfunction "IO55_55") (pintype "bidirectional"))
    )
    (net (code "82") (name "/SND2") (class "Default")
      (node (ref "R30") (pin "1") (pinfunction "1_1") (pintype "passive"))
      (node (ref "U8") (pin "53") (pinfunction "IO53_53") (pintype "bidirectional"))
    )
    (net (code "83") (name "/SND3") (class "Default")
      (node (ref "R32") (pin "1") (pinfunction "1_1") (pintype "passive"))
      (node (ref "U8") (pin "52") (pinfunction "IO52_52") (pintype "bidirectional"))
    )
    (net (code "84") (name "/SND4") (class "Default")
      (node (ref "R34") (pin "1") (pinfunction "1_1") (pintype "passive"))
      (node (ref "U8") (pin "51") (pinfunction "IO51_51") (pintype "bidirectional"))
    )
    (net (code "85") (name "/SND5") (class "Default")
      (node (ref "R36") (pin "1") (pinfunction "1_1") (pintype "passive"))
      (node (ref "U8") (pin "48") (pinfunction "IO48_48") (pintype "bidirectional"))
    )
    (net (code "86") (name "/SND_L") (class "Default")
      (node (ref "C39") (pin "1") (pinfunction "1_1") (pintype "passive"))
      (node (ref "JP1") (pin "1") (pinfunction "1_1") (pintype "passive"))
      (node (ref "JP6") (pin "2") (pinfunction "2_2") (pintype "passive"))
    )
    (net (code "87") (name "/SND_R") (class "Default")
      (node (ref "C40") (pin "1") (pinfunction "1_1") (pintype "passive"))
      (node (ref "JP5") (pin "1") (pinfunction "1_1") (pintype "passive"))
      (node (ref "JP7") (pin "2") (pinfunction "2_2") (pintype "passive"))
    )
    (net (code "88") (name "/SQA") (class "Default")
      (node (ref "R19") (pin "1") (pinfunction "1_1") (pintype "passive"))
      (node (ref "U8") (pin "86") (pinfunction "IO86_86") (pintype "bidirectional"))
    )
    (net (code "89") (name "/SQB") (class "Default")
      (node (ref "R17") (pin "1") (pinfunction "1_1") (pintype "passive"))
      (node (ref "U8") (pin "81") (pinfunction "IO81_81") (pintype "bidirectional"))
    )
    (net (code "90") (name "/TCK") (class "Default")
      (node (ref "R5") (pin "2") (pinfunction "2_2") (pintype "passive"))
      (node (ref "U8") (pin "12") (pinfunction "TCK_12") (pintype "input"))
      (node (ref "X1") (pin "1") (pinfunction "S_1") (pintype "passive"))
    )
    (net (code "91") (name "/TDI") (class "Default")
      (node (ref "R3") (pin "2") (pinfunction "2_2") (pintype "passive"))
      (node (ref "U8") (pin "13") (pinfunction "TDI_13") (pintype "input"))
      (node (ref "X1") (pin "9") (pinfunction "S_9") (pintype "passive"))
    )
    (net (code "92") (name "/TDO") (class "Default")
      (node (ref "U8") (pin "10") (pinfunction "TDO_10") (pintype "output"))
      (node (ref "X1") (pin "3") (pinfunction "S_3") (pintype "passive"))
    )
    (net (code "93") (name "/TMS") (class "Default")
      (node (ref "R4") (pin "2") (pinfunction "2_2") (pintype "passive"))
      (node (ref "U8") (pin "11") (pinfunction "TMS_11") (pintype "input"))
      (node (ref "X1") (pin "5") (pinfunction "S_5") (pintype "passive"))
    )
    (net (code "94") (name "/TRIA") (class "Default")
      (node (ref "R15") (pin "1") (pinfunction "1_1") (pintype "passive"))
      (node (ref "U8") (pin "80") (pinfunction "IO80_80") (pintype "bidirectional"))
    )
    (net (code "95") (name "/VPLL1") (class "Default")
      (node (ref "C12") (pin "1") (pinfunction "1_1") (pintype "passive"))
      (node (ref "C13") (pin "1") (pinfunction "1_1") (pintype "passive"))
      (node (ref "L2") (pin "2") (pinfunction "2_2") (pintype "passive"))
      (node (ref "U8") (pin "35") (pinfunction "PLL1_VCCD_35") (pintype "power_in"))
      (node (ref "U8") (pin "37") (pinfunction "PLL1_VCCA_37") (pintype "power_in"))
    )
    (net (code "96") (name "/VPPL2") (class "Default")
      (node (ref "C10") (pin "1") (pinfunction "1_1") (pintype "passive"))
      (node (ref "C11") (pin "1") (pinfunction "1_1") (pintype "passive"))
      (node (ref "L1") (pin "1") (pinfunction "1_1") (pintype "passive"))
      (node (ref "U8") (pin "107") (pinfunction "PLL2_VCCD_107") (pintype "power_in"))
      (node (ref "U8") (pin "109") (pinfunction "PLL2_VCCA_109") (pintype "power_in"))
    )
    (net (code "97") (name "/{slash}CSO") (class "Default")
      (node (ref "U6") (pin "1") (pinfunction "/CS_1") (pintype "input"))
      (node (ref "U8") (pin "2") (pinfunction "IO2(/CSO)_2") (pintype "output"))
    )
    (net (code "98") (name "/{slash}IN0") (class "Default")
      (node (ref "HEADER") (pin "36") (pinfunction "/IN0_36") (pintype "input"))
      (node (ref "U3") (pin "14") (pinfunction "Y5_14") (pintype "output"))
    )
    (net (code "99") (name "/{slash}IN0_FPGA") (class "Default")
      (node (ref "U3") (pin "6") (pinfunction "A5_6") (pintype "input"))
      (node (ref "U8") (pin "133") (pinfunction "IO133_133") (pintype "bidirectional"))
    )
    (net (code "100") (name "/{slash}IN1") (class "Default")
      (node (ref "HEADER") (pin "35") (pinfunction "/IN1_35") (pintype "input"))
      (node (ref "U3") (pin "13") (pinfunction "Y6_13") (pintype "output"))
    )
    (net (code "101") (name "/{slash}IN1_FPGA") (class "Default")
      (node (ref "U3") (pin "7") (pinfunction "A6_7") (pintype "input"))
      (node (ref "U8") (pin "132") (pinfunction "IO132_132") (pintype "bidirectional"))
    )
    (net (code "102") (name "/{slash}IRQ") (class "Default")
      (node (ref "HEADER") (pin "32") (pinfunction "/IRQ_32") (pintype "output"))
      (node (ref "U9") (pin "2") (pinfunction "IN_2") (pintype "bidirectional"))
    )
    (net (code "103") (name "/{slash}NMI") (class "Default")
      (node (ref "HEADER") (pin "33") (pinfunction "/NMI_33") (pintype "output"))
      (node (ref "U7") (pin "2") (pinfunction "IN_2") (pintype "bidirectional"))
    )
    (net (code "104") (name "/{slash}OE") (class "Default")
      (node (ref "U1") (pin "1") (pinfunction "/OE1_1") (pintype "input"))
      (node (ref "U2") (pin "1") (pinfunction "/OE1_1") (pintype "input"))
      (node (ref "U3") (pin "19") (pinfunction "/OE2_19") (pintype "input"))
      (node (ref "U5") (pin "22") (pinfunction "/OE_22") (pintype "input"))
      (node (ref "U8") (pin "100") (pinfunction "IO100_100") (pintype "bidirectional"))
    )
    (net (code "105") (name "/{slash}RES") (class "Default")
      (node (ref "HEADER") (pin "3") (pinfunction "/RES_3") (pintype "output"))
      (node (ref "U4") (pin "2") (pinfunction "IN_2") (pintype "bidirectional"))
    )
    (net (code "106") (name "GND") (class "Default")
      (node (ref "C1") (pin "2") (pinfunction "2_2") (pintype "passive"))
      (node (ref "C10") (pin "2") (pinfunction "2_2") (pintype "passive"))
      (node (ref "C11") (pin "2") (pinfunction "2_2") (pintype "passive"))
      (node (ref "C12") (pin "2") (pinfunction "2_2") (pintype "passive"))
      (node (ref "C13") (pin "2") (pinfunction "2_2") (pintype "passive"))
      (node (ref "C14") (pin "1") (pinfunction "1_1") (pintype "passive"))
      (node (ref "C15") (pin "1") (pinfunction "1_1") (pintype "passive"))
      (node (ref "C16") (pin "2") (pinfunction "2_2") (pintype "passive"))
      (node (ref "C17") (pin "2") (pinfunction "2_2") (pintype "passive"))
      (node (ref "C18") (pin "2") (pinfunction "2_2") (pintype "passive"))
      (node (ref "C19") (pin "2") (pinfunction "2_2") (pintype "passive"))
      (node (ref "C2") (pin "2") (pinfunction "2_2") (pintype "passive"))
      (node (ref "C20") (pin "2") (pinfunction "2_2") (pintype "passive"))
      (node (ref "C21") (pin "2") (pinfunction "2_2") (pintype "passive"))
      (node (ref "C22") (pin "2") (pinfunction "2_2") (pintype "passive"))
      (node (ref "C23") (pin "2") (pinfunction "2_2") (pintype "passive"))
      (node (ref "C24") (pin "2") (pinfunction "2_2") (pintype "passive"))
      (node (ref "C25") (pin "2") (pinfunction "2_2") (pintype "passive"))
      (node (ref "C26") (pin "2") (pinfunction "2_2") (pintype "passive"))
      (node (ref "C27") (pin "2") (pinfunction "2_2") (pintype "passive"))
      (node (ref "C28") (pin "2") (pinfunction "2_2") (pintype "passive"))
      (node (ref "C29") (pin "2") (pinfunction "2_2") (pintype "passive"))
      (node (ref "C3") (pin "2") (pinfunction "2_2") (pintype "passive"))
      (node (ref "C30") (pin "2") (pinfunction "2_2") (pintype "passive"))
      (node (ref "C31") (pin "2") (pinfunction "2_2") (pintype "passive"))
      (node (ref "C32") (pin "2") (pinfunction "2_2") (pintype "passive"))
      (node (ref "C33") (pin "2") (pinfunction "2_2") (pintype "passive"))
      (node (ref "C34") (pin "2") (pinfunction "2_2") (pintype "passive"))
      (node (ref "C35") (pin "2") (pinfunction "2_2") (pintype "passive"))
      (node (ref "C36") (pin "2") (pinfunction "2_2") (pintype "passive"))
      (node (ref "C37") (pin "2") (pinfunction "2_2") (pintype "passive"))
      (node (ref "C4") (pin "-") (pinfunction "-_-") (pintype "passive"))
      (node (ref "C41") (pin "2") (pinfunction "2_2") (pintype "passive"))
      (node (ref "C42") (pin "1") (pinfunction "1_1") (pintype "passive"))
      (node (ref "C45") (pin "2") (pinfunction "2_2") (pintype "passive"))
      (node (ref "C46") (pin "2") (pinfunction "2_2") (pintype "passive"))
      (node (ref "C5") (pin "2") (pinfunction "2_2") (pintype "passive"))
      (node (ref "C6") (pin "2") (pinfunction "2_2") (pintype "passive"))
      (node (ref "C7") (pin "2") (pinfunction "2_2") (pintype "passive"))
      (node (ref "C8") (pin "2") (pinfunction "2_2") (pintype "passive"))
      (node (ref "C9") (pin "-") (pinfunction "-_-") (pintype "passive"))
      (node (ref "HEADER") (pin "20") (pinfunction "GND_20") (pintype "power_in"))
      (node (ref "HEADER") (pin "30") (pinfunction "DBG_30") (pintype "input"))
      (node (ref "JP2") (pin "2") (pinfunction "2_2") (pintype "passive"))
      (node (ref "JP4") (pin "2") (pinfunction "2_2") (pintype "passive"))
      (node (ref "JP8") (pin "2") (pinfunction "2_2") (pintype "passive"))
      (node (ref "JP9") (pin "2") (pinfunction "2_2") (pintype "passive"))
      (node (ref "LED1") (pin "C@1") (pinfunction "C_C@1") (pintype "passive"))
      (node (ref "R25") (pin "1") (pinfunction "1_1") (pintype "passive"))
      (node (ref "R37") (pin "1") (pinfunction "1_1") (pintype "passive"))
      (node (ref "R40") (pin "1") (pinfunction "1_1") (pintype "passive"))
      (node (ref "R5") (pin "1") (pinfunction "1_1") (pintype "passive"))
      (node (ref "R56") (pin "2") (pinfunction "2_2") (pintype "passive"))
      (node (ref "R58") (pin "2") (pinfunction "2_2") (pintype "passive"))
      (node (ref "R60") (pin "2") (pinfunction "2_2") (pintype "passive"))
      (node (ref "R62") (pin "2") (pinfunction "2_2") (pintype "passive"))
      (node (ref "R7") (pin "2") (pinfunction "2_2") (pintype "passive"))
      (node (ref "U1") (pin "10") (pinfunction "GND_10") (pintype "power_in"))
      (node (ref "U1") (pin "19") (pinfunction "/OE2_19") (pintype "input"))
      (node (ref "U10") (pin "4") (pinfunction "V-_4") (pintype "power_in"))
      (node (ref "U2") (pin "10") (pinfunction "GND_10") (pintype "power_in"))
      (node (ref "U2") (pin "19") (pinfunction "/OE2_19") (pintype "input"))
      (node (ref "U3") (pin "1") (pinfunction "/OE1_1") (pintype "input"))
      (node (ref "U3") (pin "10") (pinfunction "GND_10") (pintype "power_in"))
      (node (ref "U3") (pin "2") (pinfunction "A1_2") (pintype "input"))
      (node (ref "U4") (pin "3") (pinfunction "GND_3") (pintype "bidirectional"))
      (node (ref "U5") (pin "11") (pinfunction "GND_11") (pintype "power_in"))
      (node (ref "U5") (pin "12") (pinfunction "GND_12") (pintype "power_in"))
      (node (ref "U5") (pin "13") (pinfunction "GND_13") (pintype "power_in"))
      (node (ref "U6") (pin "4") (pinfunction "GND_4") (pintype "power_in"))
      (node (ref "U7") (pin "3") (pinfunction "GND_3") (pintype "bidirectional"))
      (node (ref "U8") (pin "105") (pinfunction "GND_105") (pintype "power_in"))
      (node (ref "U8") (pin "106") (pinfunction "GND_106") (pintype "power_in"))
      (node (ref "U8") (pin "108") (pinfunction "GND_108") (pintype "power_in"))
      (node (ref "U8") (pin "110") (pinfunction "GND_110") (pintype "power_in"))
      (node (ref "U8") (pin "111") (pinfunction "GND_111") (pintype "power_in"))
      (node (ref "U8") (pin "117") (pinfunction "GND_117") (pintype "power_in"))
      (node (ref "U8") (pin "123") (pinfunction "GND_123") (pintype "power_in"))
      (node (ref "U8") (pin "128") (pinfunction "GND_128") (pintype "power_in"))
      (node (ref "U8") (pin "130") (pinfunction "GND_130") (pintype "power_in"))
      (node (ref "U8") (pin "140") (pinfunction "GND_140") (pintype "power_in"))
      (node (ref "U8") (pin "19") (pinfunction "GND_19") (pintype "power_in"))
      (node (ref "U8") (pin "33") (pinfunction "GND_33") (pintype "power_in"))
      (node (ref "U8") (pin "34") (pinfunction "GND_34") (pintype "power_in"))
      (node (ref "U8") (pin "36") (pinfunction "GND_36") (pintype "power_in"))
      (node (ref "U8") (pin "38") (pinfunction "GND_38") (pintype "power_in"))
      (node (ref "U8") (pin "39") (pinfunction "GND_39") (pintype "power_in"))
      (node (ref "U8") (pin "49") (pinfunction "GND_49") (pintype "power_in"))
      (node (ref "U8") (pin "56") (pinfunction "GND_56") (pintype "power_in"))
      (node (ref "U8") (pin "6") (pinfunction "GND_6") (pintype "power_in"))
      (node (ref "U8") (pin "61") (pinfunction "GND_61") (pintype "power_in"))
      (node (ref "U8") (pin "68") (pinfunction "GND_68") (pintype "power_in"))
      (node (ref "U8") (pin "78") (pinfunction "GND_78") (pintype "power_in"))
      (node (ref "U8") (pin "84") (pinfunction "MSEL1_84") (pintype "input"))
      (node (ref "U8") (pin "85") (pinfunction "MSEL0_85") (pintype "input"))
      (node (ref "U8") (pin "98") (pinfunction "GND_98") (pintype "power_in"))
      (node (ref "U9") (pin "3") (pinfunction "GND_3") (pintype "bidirectional"))
      (node (ref "VR1") (pin "1") (pinfunction "GND_1") (pintype "power_in"))
      (node (ref "VR2") (pin "1") (pinfunction "GND_1") (pintype "bidirectional"))
      (node (ref "X1") (pin "10") (pinfunction "S_10") (pintype "passive"))
      (node (ref "X1") (pin "2") (pinfunction "S_2") (pintype "passive"))
      (node (ref "X2") (pin "1") (pinfunction "1_1") (pintype "passive"))
      (node (ref "XO1") (pin "2") (pinfunction "GND_2") (pintype "power_in"))
      (node (ref "XO2") (pin "2") (pinfunction "GND_2") (pintype "power_in"))
    )
    (net (code "107") (name "Net-(C31-Pad1)") (class "Default")
      (node (ref "C31") (pin "1") (pinfunction "1_1") (pintype "passive"))
      (node (ref "R11") (pin "2") (pinfunction "2_2") (pintype "passive"))
      (node (ref "R12") (pin "1") (pinfunction "1_1") (pintype "passive"))
    )
    (net (code "108") (name "Net-(C32-Pad1)") (class "Default")
      (node (ref "C32") (pin "1") (pinfunction "1_1") (pintype "passive"))
      (node (ref "R13") (pin "2") (pinfunction "2_2") (pintype "passive"))
      (node (ref "R14") (pin "1") (pinfunction "1_1") (pintype "passive"))
    )
    (net (code "109") (name "Net-(C33-Pad1)") (class "Default")
      (node (ref "C33") (pin "1") (pinfunction "1_1") (pintype "passive"))
      (node (ref "R15") (pin "2") (pinfunction "2_2") (pintype "passive"))
      (node (ref "R16") (pin "1") (pinfunction "1_1") (pintype "passive"))
    )
    (net (code "110") (name "Net-(C34-Pad1)") (class "Default")
      (node (ref "C34") (pin "1") (pinfunction "1_1") (pintype "passive"))
      (node (ref "R17") (pin "2") (pinfunction "2_2") (pintype "passive"))
      (node (ref "R18") (pin "1") (pinfunction "1_1") (pintype "passive"))
    )
    (net (code "111") (name "Net-(C35-Pad1)") (class "Default")
      (node (ref "C35") (pin "1") (pinfunction "1_1") (pintype "passive"))
      (node (ref "R19") (pin "2") (pinfunction "2_2") (pintype "passive"))
      (node (ref "R20") (pin "1") (pinfunction "1_1") (pintype "passive"))
    )
    (net (code "112") (name "Net-(C38-Pad2)") (class "Default")
      (node (ref "C38") (pin "2") (pinfunction "2_2") (pintype "passive"))
      (node (ref "JP3") (pin "1") (pinfunction "1_1") (pintype "passive"))
    )
    (net (code "113") (name "Net-(C43-Pad+)") (class "Default")
      (node (ref "C43") (pin "+") (pinfunction "+_+") (pintype "passive"))
      (node (ref "R67") (pin "2") (pinfunction "2_2") (pintype "passive"))
    )
    (net (code "114") (name "Net-(C44-Pad+)") (class "Default")
      (node (ref "C44") (pin "+") (pinfunction "+_+") (pintype "passive"))
      (node (ref "R68") (pin "2") (pinfunction "2_2") (pintype "passive"))
    )
    (net (code "115") (name "Net-(C45-Pad1)") (class "Default")
      (node (ref "C45") (pin "1") (pinfunction "1_1") (pintype "passive"))
      (node (ref "C46") (pin "1") (pinfunction "1_1") (pintype "passive"))
      (node (ref "R61") (pin "2") (pinfunction "2_2") (pintype "passive"))
      (node (ref "R62") (pin "1") (pinfunction "1_1") (pintype "passive"))
      (node (ref "R63") (pin "1") (pinfunction "1_1") (pintype "passive"))
      (node (ref "R64") (pin "1") (pinfunction "1_1") (pintype "passive"))
    )
    (net (code "116") (name "Net-(JP1-Pad2)") (class "Default")
      (node (ref "JP1") (pin "2") (pinfunction "2_2") (pintype "passive"))
      (node (ref "R38") (pin "2") (pinfunction "2_2") (pintype "passive"))
      (node (ref "R54") (pin "1") (pinfunction "1_1") (pintype "passive"))
    )
    (net (code "117") (name "Net-(JP5-Pad2)") (class "Default")
      (node (ref "JP5") (pin "2") (pinfunction "2_2") (pintype "passive"))
      (node (ref "R39") (pin "2") (pinfunction "2_2") (pintype "passive"))
      (node (ref "R55") (pin "1") (pinfunction "1_1") (pintype "passive"))
    )
    (net (code "118") (name "Net-(JP6-Pad1)") (class "Default")
      (node (ref "JP6") (pin "1") (pinfunction "1_1") (pintype "passive"))
      (node (ref "R21") (pin "2") (pinfunction "2_2") (pintype "passive"))
      (node (ref "R23") (pin "1") (pinfunction "1_1") (pintype "passive"))
    )
    (net (code "119") (name "Net-(JP7-Pad1)") (class "Default")
      (node (ref "JP7") (pin "1") (pinfunction "1_1") (pintype "passive"))
      (node (ref "R22") (pin "2") (pinfunction "2_2") (pintype "passive"))
      (node (ref "R24") (pin "1") (pinfunction "1_1") (pintype "passive"))
    )
    (net (code "120") (name "Net-(LED1-A)") (class "Default")
      (node (ref "LED1") (pin "A@1") (pinfunction "A_A@1") (pintype "passive"))
      (node (ref "R10") (pin "1") (pinfunction "1_1") (pintype "passive"))
    )
    (net (code "121") (name "Net-(R12-Pad2)") (class "Default")
      (node (ref "R12") (pin "2") (pinfunction "2_2") (pintype "passive"))
      (node (ref "R14") (pin "2") (pinfunction "2_2") (pintype "passive"))
      (node (ref "R16") (pin "2") (pinfunction "2_2") (pintype "passive"))
      (node (ref "R21") (pin "1") (pinfunction "1_1") (pintype "passive"))
      (node (ref "R22") (pin "1") (pinfunction "1_1") (pintype "passive"))
    )
    (net (code "122") (name "Net-(R18-Pad2)") (class "Default")
      (node (ref "R18") (pin "2") (pinfunction "2_2") (pintype "passive"))
      (node (ref "R20") (pin "2") (pinfunction "2_2") (pintype "passive"))
      (node (ref "R23") (pin "2") (pinfunction "2_2") (pintype "passive"))
      (node (ref "R24") (pin "2") (pinfunction "2_2") (pintype "passive"))
    )
    (net (code "123") (name "Net-(R25-Pad2)") (class "Default")
      (node (ref "R25") (pin "2") (pinfunction "2_2") (pintype "passive"))
      (node (ref "R26") (pin "2") (pinfunction "2_2") (pintype "passive"))
      (node (ref "R27") (pin "1") (pinfunction "1_1") (pintype "passive"))
    )
    (net (code "124") (name "Net-(R27-Pad2)") (class "Default")
      (node (ref "R27") (pin "2") (pinfunction "2_2") (pintype "passive"))
      (node (ref "R28") (pin "2") (pinfunction "2_2") (pintype "passive"))
      (node (ref "R29") (pin "1") (pinfunction "1_1") (pintype "passive"))
    )
    (net (code "125") (name "Net-(R29-Pad2)") (class "Default")
      (node (ref "R29") (pin "2") (pinfunction "2_2") (pintype "passive"))
      (node (ref "R30") (pin "2") (pinfunction "2_2") (pintype "passive"))
      (node (ref "R31") (pin "1") (pinfunction "1_1") (pintype "passive"))
    )
    (net (code "126") (name "Net-(R31-Pad2)") (class "Default")
      (node (ref "R31") (pin "2") (pinfunction "2_2") (pintype "passive"))
      (node (ref "R32") (pin "2") (pinfunction "2_2") (pintype "passive"))
      (node (ref "R33") (pin "1") (pinfunction "1_1") (pintype "passive"))
    )
    (net (code "127") (name "Net-(R33-Pad2)") (class "Default")
      (node (ref "R33") (pin "2") (pinfunction "2_2") (pintype "passive"))
      (node (ref "R34") (pin "2") (pinfunction "2_2") (pintype "passive"))
      (node (ref "R35") (pin "1") (pinfunction "1_1") (pintype "passive"))
    )
    (net (code "128") (name "Net-(R35-Pad2)") (class "Default")
      (node (ref "R35") (pin "2") (pinfunction "2_2") (pintype "passive"))
      (node (ref "R36") (pin "2") (pinfunction "2_2") (pintype "passive"))
      (node (ref "R37") (pin "2") (pinfunction "2_2") (pintype "passive"))
      (node (ref "R38") (pin "1") (pinfunction "1_1") (pintype "passive"))
      (node (ref "R39") (pin "1") (pinfunction "1_1") (pintype "passive"))
    )
    (net (code "129") (name "Net-(R40-Pad2)") (class "Default")
      (node (ref "R40") (pin "2") (pinfunction "2_2") (pintype "passive"))
      (node (ref "R41") (pin "2") (pinfunction "2_2") (pintype "passive"))
      (node (ref "R42") (pin "1") (pinfunction "1_1") (pintype "passive"))
    )
    (net (code "130") (name "Net-(R42-Pad2)") (class "Default")
      (node (ref "R42") (pin "2") (pinfunction "2_2") (pintype "passive"))
      (node (ref "R43") (pin "2") (pinfunction "2_2") (pintype "passive"))
      (node (ref "R44") (pin "1") (pinfunction "1_1") (pintype "passive"))
    )
    (net (code "131") (name "Net-(R44-Pad2)") (class "Default")
      (node (ref "R44") (pin "2") (pinfunction "2_2") (pintype "passive"))
      (node (ref "R45") (pin "2") (pinfunction "2_2") (pintype "passive"))
      (node (ref "R46") (pin "1") (pinfunction "1_1") (pintype "passive"))
    )
    (net (code "132") (name "Net-(R46-Pad2)") (class "Default")
      (node (ref "R46") (pin "2") (pinfunction "2_2") (pintype "passive"))
      (node (ref "R47") (pin "2") (pinfunction "2_2") (pintype "passive"))
      (node (ref "R48") (pin "1") (pinfunction "1_1") (pintype "passive"))
    )
    (net (code "133") (name "Net-(R48-Pad2)") (class "Default")
      (node (ref "R48") (pin "2") (pinfunction "2_2") (pintype "passive"))
      (node (ref "R49") (pin "2") (pinfunction "2_2") (pintype "passive"))
      (node (ref "R50") (pin "1") (pinfunction "1_1") (pintype "passive"))
    )
    (net (code "134") (name "Net-(R50-Pad2)") (class "Default")
      (node (ref "R50") (pin "2") (pinfunction "2_2") (pintype "passive"))
      (node (ref "R51") (pin "2") (pinfunction "2_2") (pintype "passive"))
      (node (ref "R52") (pin "1") (pinfunction "1_1") (pintype "passive"))
    )
    (net (code "135") (name "Net-(R52-Pad2)") (class "Default")
      (node (ref "R52") (pin "2") (pinfunction "2_2") (pintype "passive"))
      (node (ref "R53") (pin "2") (pinfunction "2_2") (pintype "passive"))
      (node (ref "R54") (pin "2") (pinfunction "2_2") (pintype "passive"))
      (node (ref "R55") (pin "2") (pinfunction "2_2") (pintype "passive"))
      (node (ref "R56") (pin "1") (pinfunction "1_1") (pintype "passive"))
    )
    (net (code "136") (name "Net-(U8-CONF_DONE)") (class "Default")
      (node (ref "R6") (pin "1") (pinfunction "1_1") (pintype "passive"))
      (node (ref "U8") (pin "83") (pinfunction "CONF_DONE_83") (pintype "input"))
    )
    (net (code "137") (name "Net-(U8-IO27)") (class "Default")
      (node (ref "JP4") (pin "1") (pinfunction "1_1") (pintype "passive"))
      (node (ref "U8") (pin "27") (pinfunction "IO27_27") (pintype "bidirectional"))
    )
    (net (code "138") (name "Net-(U8-IO28)") (class "Default")
      (node (ref "JP9") (pin "1") (pinfunction "1_1") (pintype "passive"))
      (node (ref "U8") (pin "28") (pinfunction "IO28_28") (pintype "bidirectional"))
    )
    (net (code "139") (name "Net-(U8-IO30)") (class "Default")
      (node (ref "JP8") (pin "1") (pinfunction "1_1") (pintype "passive"))
      (node (ref "U8") (pin "30") (pinfunction "IO30_30") (pintype "bidirectional"))
    )
    (net (code "140") (name "Net-(U8-IO31)") (class "Default")
      (node (ref "JP2") (pin "1") (pinfunction "1_1") (pintype "passive"))
      (node (ref "U8") (pin "31") (pinfunction "IO31_31") (pintype "bidirectional"))
    )
    (net (code "141") (name "Net-(U8-NCE)") (class "Default")
      (node (ref "R7") (pin "1") (pinfunction "1_1") (pintype "passive"))
      (node (ref "U8") (pin "16") (pinfunction "NCE_16") (pintype "input"))
    )
    (net (code "142") (name "Net-(U8-NCONFIG)") (class "Default")
      (node (ref "R8") (pin "1") (pinfunction "1_1") (pintype "passive"))
      (node (ref "U8") (pin "20") (pinfunction "NCONFIG_20") (pintype "input"))
    )
    (net (code "143") (name "Net-(U8-NSTATUS)") (class "Default")
      (node (ref "R9") (pin "1") (pinfunction "1_1") (pintype "passive"))
      (node (ref "U8") (pin "82") (pinfunction "NSTATUS_82") (pintype "input"))
    )
    (net (code "144") (name "Net-(U10A-+IN)") (class "Default")
      (node (ref "C39") (pin "2") (pinfunction "2_2") (pintype "passive"))
      (node (ref "R57") (pin "2") (pinfunction "2_2") (pintype "passive"))
      (node (ref "R58") (pin "1") (pinfunction "1_1") (pintype "passive"))
      (node (ref "U10") (pin "3") (pinfunction "+IN_3") (pintype "input"))
    )
    (net (code "145") (name "Net-(U10A--IN)") (class "Default")
      (node (ref "R63") (pin "2") (pinfunction "2_2") (pintype "passive"))
      (node (ref "R65") (pin "1") (pinfunction "1_1") (pintype "passive"))
      (node (ref "U10") (pin "2") (pinfunction "-IN_2") (pintype "input"))
    )
    (net (code "146") (name "Net-(U10A-OUT)") (class "Default")
      (node (ref "R65") (pin "2") (pinfunction "2_2") (pintype "passive"))
      (node (ref "R67") (pin "1") (pinfunction "1_1") (pintype "passive"))
      (node (ref "U10") (pin "1") (pinfunction "OUT_1") (pintype "output"))
    )
    (net (code "147") (name "Net-(U10B-+IN)") (class "Default")
      (node (ref "C40") (pin "2") (pinfunction "2_2") (pintype "passive"))
      (node (ref "R59") (pin "2") (pinfunction "2_2") (pintype "passive"))
      (node (ref "R60") (pin "1") (pinfunction "1_1") (pintype "passive"))
      (node (ref "U10") (pin "5") (pinfunction "+IN_5") (pintype "input"))
    )
    (net (code "148") (name "Net-(U10B--IN)") (class "Default")
      (node (ref "R64") (pin "2") (pinfunction "2_2") (pintype "passive"))
      (node (ref "R66") (pin "1") (pinfunction "1_1") (pintype "passive"))
      (node (ref "U10") (pin "6") (pinfunction "-IN_6") (pintype "input"))
    )
    (net (code "149") (name "Net-(U10B-OUT)") (class "Default")
      (node (ref "R66") (pin "2") (pinfunction "2_2") (pintype "passive"))
      (node (ref "R68") (pin "1") (pinfunction "1_1") (pintype "passive"))
      (node (ref "U10") (pin "7") (pinfunction "OUT_7") (pintype "output"))
    )
    (net (code "150") (name "Net-(X2B-1)") (class "Default")
      (node (ref "C43") (pin "-") (pinfunction "-_-") (pintype "passive"))
      (node (ref "X2") (pin "2") (pinfunction "1_2") (pintype "passive"))
    )
    (net (code "151") (name "Net-(X2C-1)") (class "Default")
      (node (ref "C44") (pin "-") (pinfunction "-_-") (pintype "passive"))
      (node (ref "X2") (pin "3") (pinfunction "1_3") (pintype "passive"))
    )
    (net (code "152") (name "Net-(XO1-OUT)") (class "Default")
      (node (ref "C38") (pin "1") (pinfunction "1_1") (pintype "passive"))
      (node (ref "R1") (pin "1") (pinfunction "1_1") (pintype "passive"))
      (node (ref "XO1") (pin "3") (pinfunction "OUT_3") (pintype "output"))
    )
    (net (code "153") (name "Net-(XO1-VDD)") (class "Default")
      (node (ref "C36") (pin "1") (pinfunction "1_1") (pintype "passive"))
      (node (ref "L3") (pin "2") (pinfunction "2_2") (pintype "passive"))
      (node (ref "XO1") (pin "4") (pinfunction "VDD_4") (pintype "power_in"))
    )
    (net (code "154") (name "VCCINT") (class "Default")
      (node (ref "C27") (pin "1") (pinfunction "1_1") (pintype "passive"))
      (node (ref "C28") (pin "1") (pinfunction "1_1") (pintype "passive"))
      (node (ref "C29") (pin "1") (pinfunction "1_1") (pintype "passive"))
      (node (ref "C30") (pin "1") (pinfunction "1_1") (pintype "passive"))
      (node (ref "C8") (pin "1") (pinfunction "1_1") (pintype "passive"))
      (node (ref "C9") (pin "+") (pinfunction "+_+") (pintype "passive"))
      (node (ref "L1") (pin "2") (pinfunction "2_2") (pintype "passive"))
      (node (ref "L2") (pin "1") (pinfunction "1_1") (pintype "passive"))
      (node (ref "U8") (pin "124") (pinfunction "VCCINT_124") (pintype "power_in"))
      (node (ref "U8") (pin "131") (pinfunction "VCCINT_131") (pintype "power_in"))
      (node (ref "U8") (pin "50") (pinfunction "VCCINT_50") (pintype "power_in"))
      (node (ref "U8") (pin "62") (pinfunction "VCCINT_62") (pintype "power_in"))
      (node (ref "VR2") (pin "2") (pinfunction "VOUT_2") (pintype "bidirectional"))
    )
    (net (code "155") (name "VCCIO") (class "Default")
      (node (ref "C14") (pin "2") (pinfunction "2_2") (pintype "passive"))
      (node (ref "C16") (pin "1") (pinfunction "1_1") (pintype "passive"))
      (node (ref "C17") (pin "1") (pinfunction "1_1") (pintype "passive"))
      (node (ref "C18") (pin "1") (pinfunction "1_1") (pintype "passive"))
      (node (ref "C19") (pin "1") (pinfunction "1_1") (pintype "passive"))
      (node (ref "C20") (pin "1") (pinfunction "1_1") (pintype "passive"))
      (node (ref "C21") (pin "1") (pinfunction "1_1") (pintype "passive"))
      (node (ref "C22") (pin "1") (pinfunction "1_1") (pintype "passive"))
      (node (ref "C23") (pin "1") (pinfunction "1_1") (pintype "passive"))
      (node (ref "C24") (pin "1") (pinfunction "1_1") (pintype "passive"))
      (node (ref "C25") (pin "1") (pinfunction "1_1") (pintype "passive"))
      (node (ref "C26") (pin "1") (pinfunction "1_1") (pintype "passive"))
      (node (ref "C37") (pin "1") (pinfunction "1_1") (pintype "passive"))
      (node (ref "C6") (pin "1") (pinfunction "1_1") (pintype "passive"))
      (node (ref "C7") (pin "1") (pinfunction "1_1") (pintype "passive"))
      (node (ref "L3") (pin "1") (pinfunction "1_1") (pintype "passive"))
      (node (ref "R3") (pin "1") (pinfunction "1_1") (pintype "passive"))
      (node (ref "R4") (pin "1") (pinfunction "1_1") (pintype "passive"))
      (node (ref "R6") (pin "2") (pinfunction "2_2") (pintype "passive"))
      (node (ref "R8") (pin "2") (pinfunction "2_2") (pintype "passive"))
      (node (ref "R9") (pin "2") (pinfunction "2_2") (pintype "passive"))
      (node (ref "U4") (pin "5") (pinfunction "VCC_5") (pintype "bidirectional"))
      (node (ref "U5") (pin "1") (pinfunction "VCCA_1") (pintype "power_in"))
      (node (ref "U6") (pin "3") (pinfunction "VCC_3") (pintype "power_in"))
      (node (ref "U6") (pin "7") (pinfunction "VCC_7") (pintype "power_in"))
      (node (ref "U6") (pin "8") (pinfunction "VCC_8") (pintype "power_in"))
      (node (ref "U7") (pin "5") (pinfunction "VCC_5") (pintype "bidirectional"))
      (node (ref "U8") (pin "102") (pinfunction "VCCIO3_102") (pintype "power_in"))
      (node (ref "U8") (pin "116") (pinfunction "VCCIO2_116") (pintype "power_in"))
      (node (ref "U8") (pin "127") (pinfunction "VCCIO2_127") (pintype "power_in"))
      (node (ref "U8") (pin "138") (pinfunction "VCCIO2_138") (pintype "power_in"))
      (node (ref "U8") (pin "23") (pinfunction "VCCIO1_23") (pintype "power_in"))
      (node (ref "U8") (pin "29") (pinfunction "VCCIO1_29") (pintype "power_in"))
      (node (ref "U8") (pin "46") (pinfunction "VCCIO4_46") (pintype "power_in"))
      (node (ref "U8") (pin "5") (pinfunction "VCCIO1_5") (pintype "power_in"))
      (node (ref "U8") (pin "54") (pinfunction "VCCIO4_54") (pintype "power_in"))
      (node (ref "U8") (pin "66") (pinfunction "VCCIO4_66") (pintype "power_in"))
      (node (ref "U8") (pin "77") (pinfunction "VCCIO3_77") (pintype "power_in"))
      (node (ref "U8") (pin "95") (pinfunction "VCCIO3_95") (pintype "power_in"))
      (node (ref "U9") (pin "5") (pinfunction "VCC_5") (pintype "bidirectional"))
      (node (ref "VR1") (pin "2") (pinfunction "VOUT_2") (pintype "power_in"))
      (node (ref "VR2") (pin "3") (pinfunction "VIN_3") (pintype "bidirectional"))
      (node (ref "X1") (pin "4") (pinfunction "S_4") (pintype "passive"))
      (node (ref "XO2") (pin "4") (pinfunction "VDD_4") (pintype "power_in"))
    )
    (net (code "156") (name "unconnected-(HEADER-AUX1-Pad1)") (class "Default")
      (node (ref "HEADER") (pin "1") (pinfunction "AUX1_1") (pintype "bidirectional"))
    )
    (net (code "157") (name "unconnected-(HEADER-AUX2-Pad2)") (class "Default")
      (node (ref "HEADER") (pin "2") (pinfunction "AUX2_2") (pintype "bidirectional"))
    )
    (net (code "158") (name "unconnected-(U3-Y1-Pad18)") (class "Default")
      (node (ref "U3") (pin "18") (pinfunction "Y1_18") (pintype "output"))
    )
    (net (code "159") (name "unconnected-(U8-CLK3-Pad22)") (class "Default")
      (node (ref "U8") (pin "22") (pinfunction "CLK3_22") (pintype "bidirectional"))
    )
    (net (code "160") (name "unconnected-(U8-CLK4-Pad91)") (class "Default")
      (node (ref "U8") (pin "91") (pinfunction "CLK4_91") (pintype "bidirectional"))
    )
    (net (code "161") (name "unconnected-(U8-CLK5-Pad90)") (class "Default")
      (node (ref "U8") (pin "90") (pinfunction "CLK5_90") (pintype "bidirectional"))
    )
    (net (code "162") (name "unconnected-(U8-CLK6-Pad89)") (class "Default")
      (node (ref "U8") (pin "89") (pinfunction "CLK6_89") (pintype "bidirectional"))
    )
    (net (code "163") (name "unconnected-(U8-CLK7-Pad88)") (class "Default")
      (node (ref "U8") (pin "88") (pinfunction "CLK7_88") (pintype "bidirectional"))
    )
    (net (code "164") (name "unconnected-(U8-IO32-Pad32)") (class "Default")
      (node (ref "U8") (pin "32") (pinfunction "IO32_32") (pintype "bidirectional"))
    )
    (net (code "165") (name "unconnected-(U8-IO58-Pad58)") (class "Default")
      (node (ref "U8") (pin "58") (pinfunction "IO58_58") (pintype "bidirectional"))
    )
    (net (code "166") (name "unconnected-(U8-IO59-Pad59)") (class "Default")
      (node (ref "U8") (pin "59") (pinfunction "IO59_59") (pintype "bidirectional"))
    )
    (net (code "167") (name "unconnected-(U8-IO60-Pad60)") (class "Default")
      (node (ref "U8") (pin "60") (pinfunction "IO60_60") (pintype "bidirectional"))
    )
    (net (code "168") (name "unconnected-(U8-IO63-Pad63)") (class "Default")
      (node (ref "U8") (pin "63") (pinfunction "IO63_63") (pintype "bidirectional"))
    )
    (net (code "169") (name "unconnected-(U8-IO64-Pad64)") (class "Default")
      (node (ref "U8") (pin "64") (pinfunction "IO64_64") (pintype "bidirectional"))
    )
    (net (code "170") (name "unconnected-(U8-IO65-Pad65)") (class "Default")
      (node (ref "U8") (pin "65") (pinfunction "IO65_65") (pintype "bidirectional"))
    )
    (net (code "171") (name "unconnected-(U8-IO67-Pad67)") (class "Default")
      (node (ref "U8") (pin "67") (pinfunction "IO67_67") (pintype "bidirectional"))
    )
    (net (code "172") (name "unconnected-(U8-IO69-Pad69)") (class "Default")
      (node (ref "U8") (pin "69") (pinfunction "IO69_69") (pintype "bidirectional"))
    )
    (net (code "173") (name "unconnected-(U8-IO70-Pad70)") (class "Default")
      (node (ref "U8") (pin "70") (pinfunction "IO70_70") (pintype "bidirectional"))
    )
    (net (code "174") (name "unconnected-(U8-IO71-Pad71)") (class "Default")
      (node (ref "U8") (pin "71") (pinfunction "IO71_71") (pintype "bidirectional"))
    )
    (net (code "175") (name "unconnected-(U8-IO72-Pad72)") (class "Default")
      (node (ref "U8") (pin "72") (pinfunction "IO72_72") (pintype "bidirectional"))
    )
    (net (code "176") (name "unconnected-(U8-IO73-Pad73)") (class "Default")
      (node (ref "U8") (pin "73") (pinfunction "IO73_73") (pintype "bidirectional"))
    )
    (net (code "177") (name "unconnected-(U8-IO74-Pad74)") (class "Default")
      (node (ref "U8") (pin "74") (pinfunction "IO74_74") (pintype "bidirectional"))
    )
    (net (code "178") (name "unconnected-(U8-IO79-Pad79)") (class "Default")
      (node (ref "U8") (pin "79") (pinfunction "IO79_79") (pintype "bidirectional"))
    )
    (net (code "179") (name "unconnected-(U8-IO87-Pad87)") (class "Default")
      (node (ref "U8") (pin "87") (pinfunction "IO87_87") (pintype "bidirectional"))
    )
    (net (code "180") (name "unconnected-(U8-IO92-Pad92)") (class "Default")
      (node (ref "U8") (pin "92") (pinfunction "IO92_92") (pintype "bidirectional"))
    )
    (net (code "181") (name "unconnected-(U8-IO93-Pad93)") (class "Default")
      (node (ref "U8") (pin "93") (pinfunction "IO93_93") (pintype "bidirectional"))
    )
    (net (code "182") (name "unconnected-(U8-IO94-Pad94)") (class "Default")
      (node (ref "U8") (pin "94") (pinfunction "IO94_94") (pintype "bidirectional"))
    )
    (net (code "183") (name "unconnected-(U8-IO96-Pad96)") (class "Default")
      (node (ref "U8") (pin "96") (pinfunction "IO96_96") (pintype "bidirectional"))
    )
    (net (code "184") (name "unconnected-(U8-IO97-Pad97)") (class "Default")
      (node (ref "U8") (pin "97") (pinfunction "IO97_97") (pintype "bidirectional"))
    )
    (net (code "185") (name "unconnected-(X1G-S-Pad6)") (class "Default")
      (node (ref "X1") (pin "6") (pinfunction "S_6") (pintype "passive"))
    )
    (net (code "186") (name "unconnected-(X1H-S-Pad7)") (class "Default")
      (node (ref "X1") (pin "7") (pinfunction "S_7") (pintype "passive"))
    )
    (net (code "187") (name "unconnected-(X1I-S-Pad8)") (class "Default")
      (node (ref "X1") (pin "8") (pinfunction "S_8") (pintype "passive"))
    )
    (net (code "188") (name "unconnected-(XO1-TS-Pad1)") (class "Default")
      (node (ref "XO1") (pin "1") (pinfunction "TS_1") (pintype "passive"))
    )
    (net (code "189") (name "unconnected-(XO2-TS-Pad1)") (class "Default")
      (node (ref "XO2") (pin "1") (pinfunction "TS_1") (pintype "passive"))
    )
  )
)
